# R3-URC18-V1.net
KiCad netlist of a schematic drawn in EAGLE
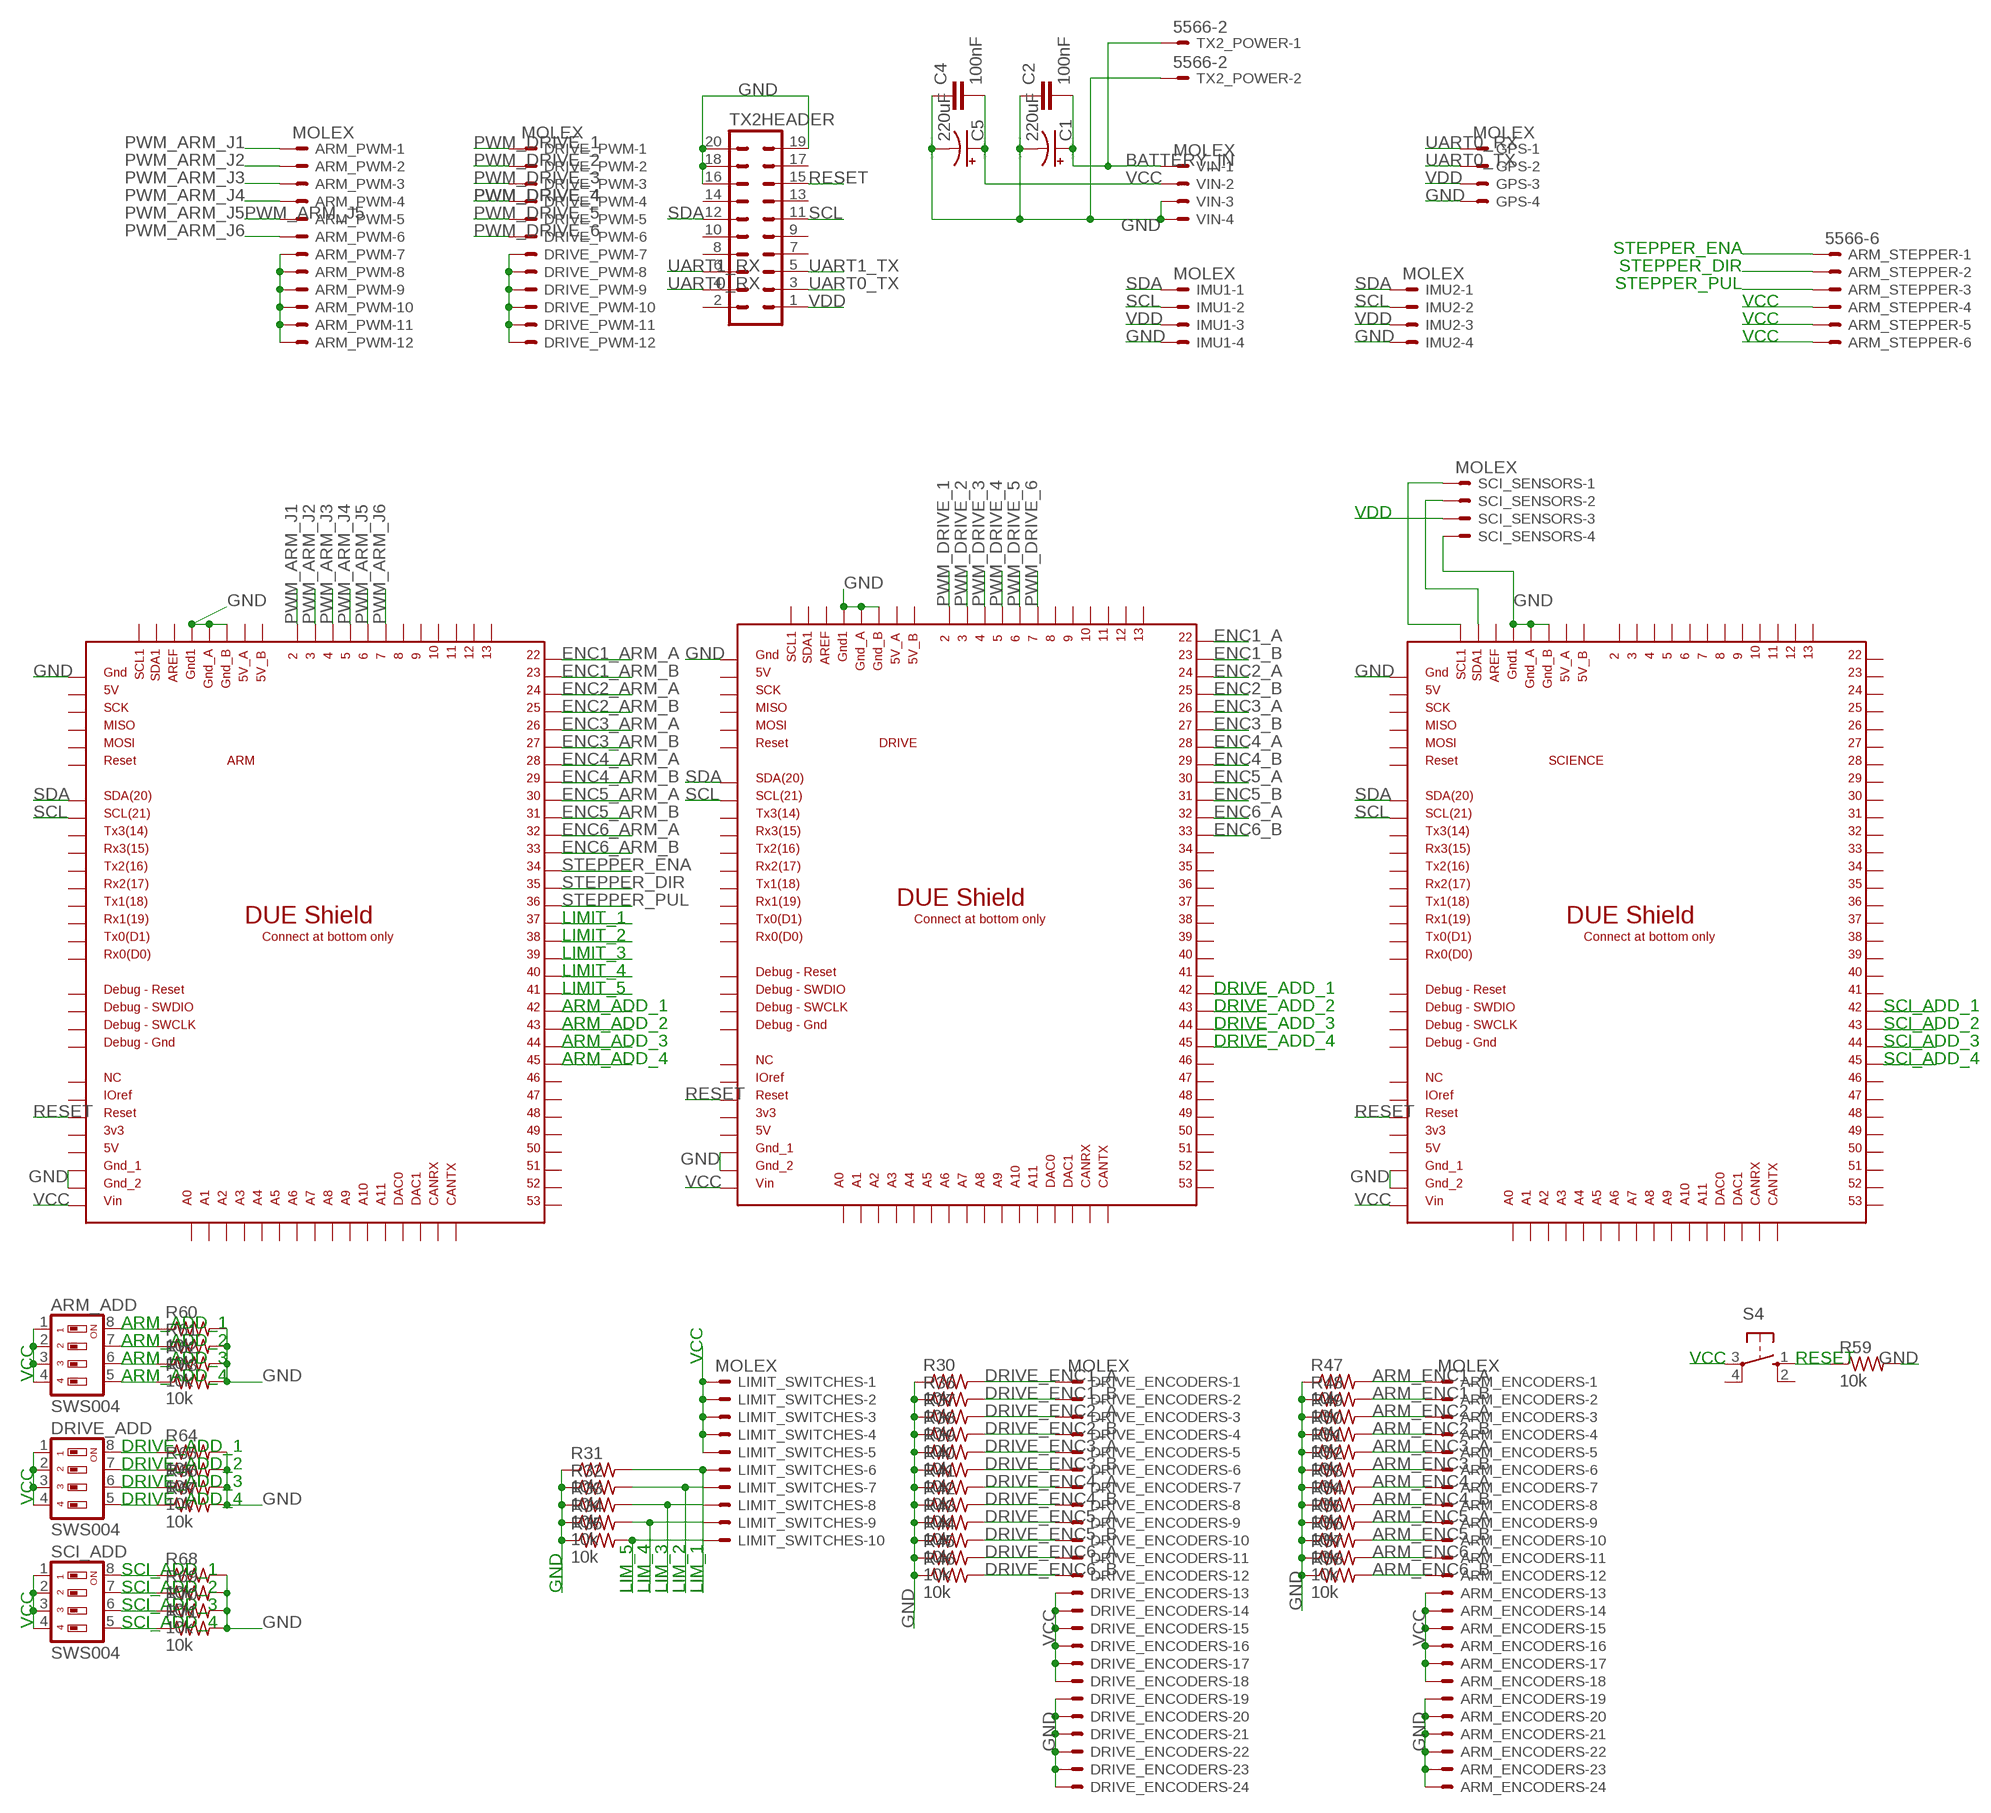
[diagram p0: schematic, sheet 1, part 1 of 2]
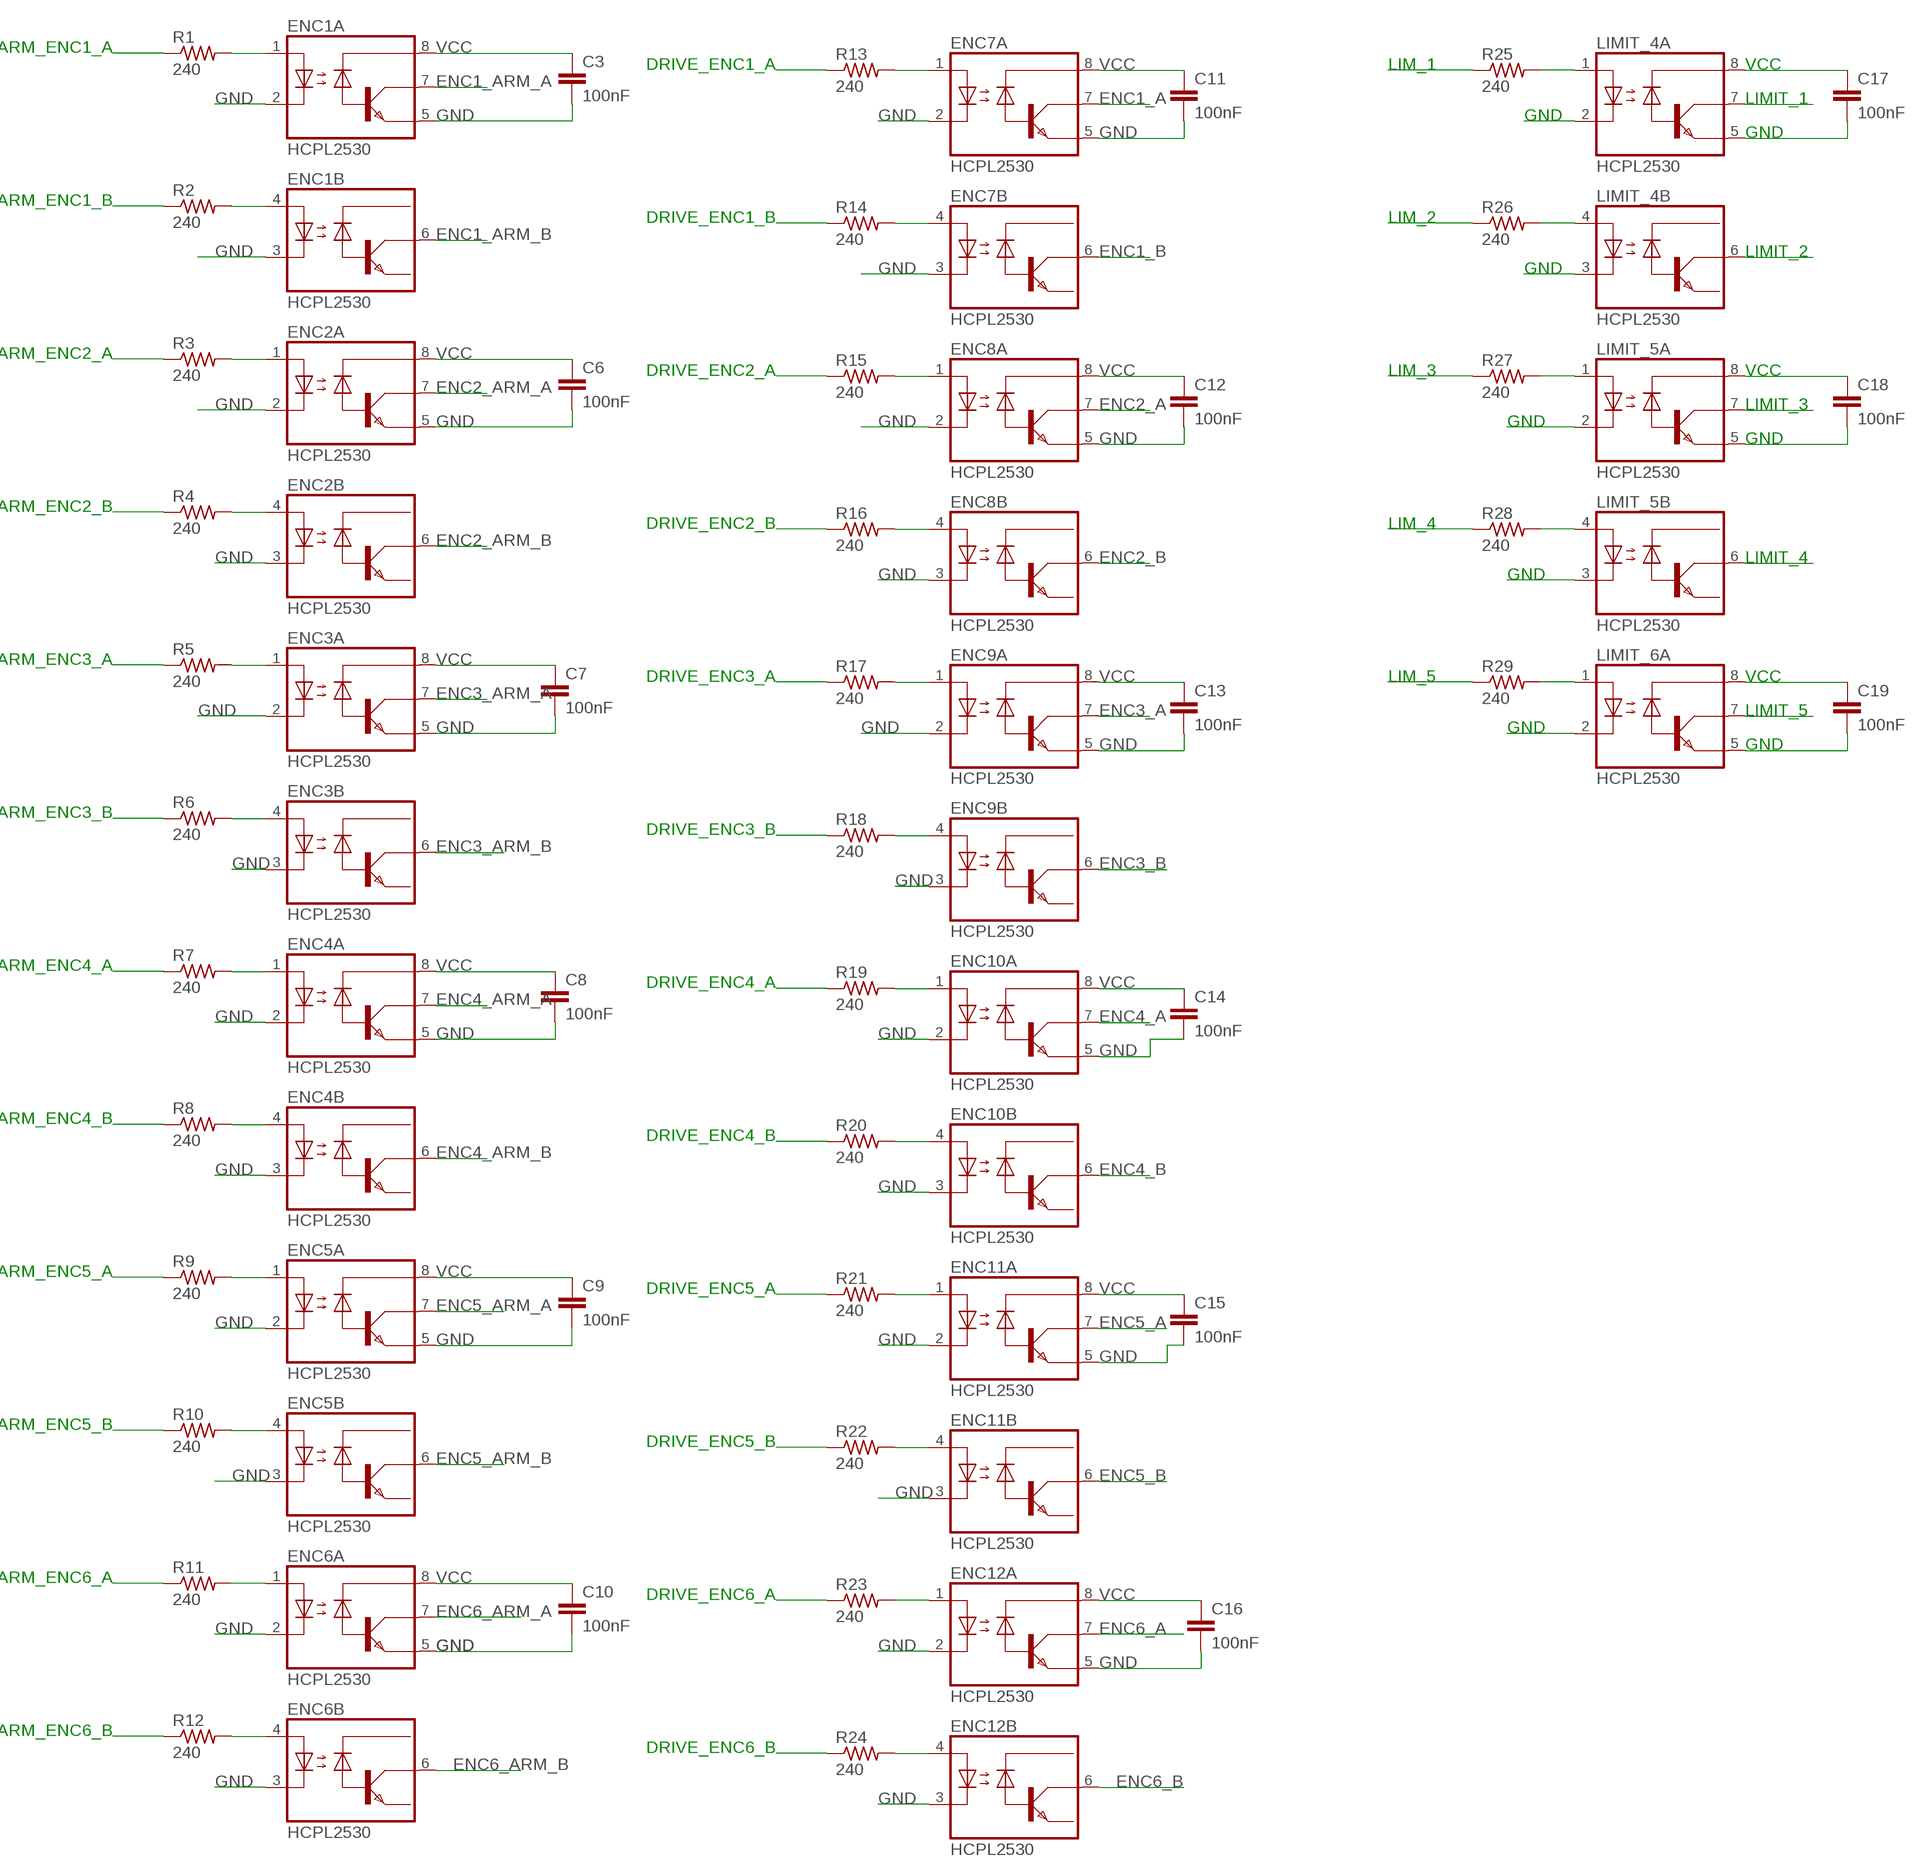
[diagram p1: schematic, sheet 1, part 2 of 2]

(export (version "E")
  (design (tool "Eeschema 10.0.6"))
  (components
    (comp (ref "ARM")
      (value "DUE(BOTTOMONLY)")
      (footprint "eagle-import:DUE(BOTTOMONLY)")
      (libsource (lib "eagle-import") (part "DUE(BOTTOMONLY)"))
    )
    (comp (ref "ARM_ADD")
      (value "SWS004")
      (footprint "eagle-import:SMS-004")
      (libsource (lib "eagle-import") (part "SWS004"))
    )
    (comp (ref "ARM_ENCODERS")
      (value "MOLEX")
      (footprint "eagle-import:5566-24")
      (libsource (lib "eagle-import") (part "5566-24"))
    )
    (comp (ref "ARM_PWM")
      (value "MOLEX")
      (footprint "eagle-import:5566-12")
      (libsource (lib "eagle-import") (part "5566-12"))
    )
    (comp (ref "ARM_STEPPER")
      (value "5566-6")
      (footprint "eagle-import:5566-6")
      (fields (field (name "MF") "MOLEX") (field (name "MPN") "95566-61002"))
      (libsource (lib "eagle-import") (part "5566-6"))
    )
    (comp (ref "C1")
      (value "220uF")
      (footprint "eagle-import:E7,5-18")
      (libsource (lib "eagle-import") (part "CPOL-USE7.5-18"))
    )
    (comp (ref "C2")
      (value "100nF")
      (footprint "eagle-import:C2.5-5")
      (libsource (lib "eagle-import") (part "C2.5/5"))
    )
    (comp (ref "C3")
      (value "100nF")
      (footprint "eagle-import:C2.5-5")
      (libsource (lib "eagle-import") (part "C2.5/5"))
    )
    (comp (ref "C4")
      (value "100nF")
      (footprint "eagle-import:C2.5-5")
      (libsource (lib "eagle-import") (part "C2.5/5"))
    )
    (comp (ref "C5")
      (value "220uF")
      (footprint "eagle-import:E7,5-18")
      (libsource (lib "eagle-import") (part "CPOL-USE7.5-18"))
    )
    (comp (ref "C6")
      (value "100nF")
      (footprint "eagle-import:C2.5-5")
      (libsource (lib "eagle-import") (part "C2.5/5"))
    )
    (comp (ref "C7")
      (value "100nF")
      (footprint "eagle-import:C2.5-5")
      (libsource (lib "eagle-import") (part "C2.5/5"))
    )
    (comp (ref "C8")
      (value "100nF")
      (footprint "eagle-import:C2.5-5")
      (libsource (lib "eagle-import") (part "C2.5/5"))
    )
    (comp (ref "C9")
      (value "100nF")
      (footprint "eagle-import:C2.5-5")
      (libsource (lib "eagle-import") (part "C2.5/5"))
    )
    (comp (ref "C10")
      (value "100nF")
      (footprint "eagle-import:C2.5-5")
      (libsource (lib "eagle-import") (part "C2.5/5"))
    )
    (comp (ref "C11")
      (value "100nF")
      (footprint "eagle-import:C2.5-5")
      (libsource (lib "eagle-import") (part "C2.5/5"))
    )
    (comp (ref "C12")
      (value "100nF")
      (footprint "eagle-import:C2.5-5")
      (libsource (lib "eagle-import") (part "C2.5/5"))
    )
    (comp (ref "C13")
      (value "100nF")
      (footprint "eagle-import:C2.5-5")
      (libsource (lib "eagle-import") (part "C2.5/5"))
    )
    (comp (ref "C14")
      (value "100nF")
      (footprint "eagle-import:C2.5-5")
      (libsource (lib "eagle-import") (part "C2.5/5"))
    )
    (comp (ref "C15")
      (value "100nF")
      (footprint "eagle-import:C2.5-5")
      (libsource (lib "eagle-import") (part "C2.5/5"))
    )
    (comp (ref "C16")
      (value "100nF")
      (footprint "eagle-import:C2.5-5")
      (libsource (lib "eagle-import") (part "C2.5/5"))
    )
    (comp (ref "C17")
      (value "100nF")
      (footprint "eagle-import:C2.5-5")
      (libsource (lib "eagle-import") (part "C2.5/5"))
    )
    (comp (ref "C18")
      (value "100nF")
      (footprint "eagle-import:C2.5-5")
      (libsource (lib "eagle-import") (part "C2.5/5"))
    )
    (comp (ref "C19")
      (value "100nF")
      (footprint "eagle-import:C2.5-5")
      (libsource (lib "eagle-import") (part "C2.5/5"))
    )
    (comp (ref "DRIVE")
      (value "DUE(BOTTOMONLY)")
      (footprint "eagle-import:DUE(BOTTOMONLY)")
      (libsource (lib "eagle-import") (part "DUE(BOTTOMONLY)"))
    )
    (comp (ref "DRIVE_ADD")
      (value "SWS004")
      (footprint "eagle-import:SMS-004")
      (libsource (lib "eagle-import") (part "SWS004"))
    )
    (comp (ref "DRIVE_ENCODERS")
      (value "MOLEX")
      (footprint "eagle-import:5566-24")
      (libsource (lib "eagle-import") (part "5566-24"))
    )
    (comp (ref "DRIVE_PWM")
      (value "MOLEX")
      (footprint "eagle-import:5566-12")
      (libsource (lib "eagle-import") (part "5566-12"))
    )
    (comp (ref "ENC1")
      (value "HCPL2530")
      (footprint "eagle-import:DIL08")
      (fields (field (name "MF") "AGILENT TECHNOLOGIES") (field (name "MPN") "HCPL-2530-000E"))
      (libsource (lib "eagle-import") (part "HCPL2530"))
    )
    (comp (ref "ENC2")
      (value "HCPL2530")
      (footprint "eagle-import:DIL08")
      (fields (field (name "MF") "AGILENT TECHNOLOGIES") (field (name "MPN") "HCPL-2530-000E"))
      (libsource (lib "eagle-import") (part "HCPL2530"))
    )
    (comp (ref "ENC3")
      (value "HCPL2530")
      (footprint "eagle-import:DIL08")
      (fields (field (name "MF") "AGILENT TECHNOLOGIES") (field (name "MPN") "HCPL-2530-000E"))
      (libsource (lib "eagle-import") (part "HCPL2530"))
    )
    (comp (ref "ENC4")
      (value "HCPL2530")
      (footprint "eagle-import:DIL08")
      (fields (field (name "MF") "AGILENT TECHNOLOGIES") (field (name "MPN") "HCPL-2530-000E"))
      (libsource (lib "eagle-import") (part "HCPL2530"))
    )
    (comp (ref "ENC5")
      (value "HCPL2530")
      (footprint "eagle-import:DIL08")
      (fields (field (name "MF") "AGILENT TECHNOLOGIES") (field (name "MPN") "HCPL-2530-000E"))
      (libsource (lib "eagle-import") (part "HCPL2530"))
    )
    (comp (ref "ENC6")
      (value "HCPL2530")
      (footprint "eagle-import:DIL08")
      (fields (field (name "MF") "AGILENT TECHNOLOGIES") (field (name "MPN") "HCPL-2530-000E"))
      (libsource (lib "eagle-import") (part "HCPL2530"))
    )
    (comp (ref "ENC7")
      (value "HCPL2530")
      (footprint "eagle-import:DIL08")
      (fields (field (name "MF") "AGILENT TECHNOLOGIES") (field (name "MPN") "HCPL-2530-000E"))
      (libsource (lib "eagle-import") (part "HCPL2530"))
    )
    (comp (ref "ENC8")
      (value "HCPL2530")
      (footprint "eagle-import:DIL08")
      (fields (field (name "MF") "AGILENT TECHNOLOGIES") (field (name "MPN") "HCPL-2530-000E"))
      (libsource (lib "eagle-import") (part "HCPL2530"))
    )
    (comp (ref "ENC9")
      (value "HCPL2530")
      (footprint "eagle-import:DIL08")
      (fields (field (name "MF") "AGILENT TECHNOLOGIES") (field (name "MPN") "HCPL-2530-000E"))
      (libsource (lib "eagle-import") (part "HCPL2530"))
    )
    (comp (ref "ENC10")
      (value "HCPL2530")
      (footprint "eagle-import:DIL08")
      (fields (field (name "MF") "AGILENT TECHNOLOGIES") (field (name "MPN") "HCPL-2530-000E"))
      (libsource (lib "eagle-import") (part "HCPL2530"))
    )
    (comp (ref "ENC11")
      (value "HCPL2530")
      (footprint "eagle-import:DIL08")
      (fields (field (name "MF") "AGILENT TECHNOLOGIES") (field (name "MPN") "HCPL-2530-000E"))
      (libsource (lib "eagle-import") (part "HCPL2530"))
    )
    (comp (ref "ENC12")
      (value "HCPL2530")
      (footprint "eagle-import:DIL08")
      (fields (field (name "MF") "AGILENT TECHNOLOGIES") (field (name "MPN") "HCPL-2530-000E"))
      (libsource (lib "eagle-import") (part "HCPL2530"))
    )
    (comp (ref "GPS")
      (value "MOLEX")
      (footprint "eagle-import:5566-4")
      (libsource (lib "eagle-import") (part "5566-4"))
    )
    (comp (ref "IMU1")
      (value "MOLEX")
      (footprint "eagle-import:5566-4")
      (libsource (lib "eagle-import") (part "5566-4"))
    )
    (comp (ref "IMU2")
      (value "MOLEX")
      (footprint "eagle-import:5566-4")
      (libsource (lib "eagle-import") (part "5566-4"))
    )
    (comp (ref "LIMIT_4")
      (value "HCPL2530")
      (footprint "eagle-import:DIL08")
      (fields (field (name "MF") "AGILENT TECHNOLOGIES") (field (name "MPN") "HCPL-2530-000E"))
      (libsource (lib "eagle-import") (part "HCPL2530"))
    )
    (comp (ref "LIMIT_5")
      (value "HCPL2530")
      (footprint "eagle-import:DIL08")
      (fields (field (name "MF") "AGILENT TECHNOLOGIES") (field (name "MPN") "HCPL-2530-000E"))
      (libsource (lib "eagle-import") (part "HCPL2530"))
    )
    (comp (ref "LIMIT_6")
      (value "HCPL2530")
      (footprint "eagle-import:DIL08")
      (fields (field (name "MF") "AGILENT TECHNOLOGIES") (field (name "MPN") "HCPL-2530-000E"))
      (libsource (lib "eagle-import") (part "HCPL2530"))
    )
    (comp (ref "LIMIT_SWITCHES")
      (value "MOLEX")
      (footprint "eagle-import:5566-10")
      (libsource (lib "eagle-import") (part "5566-10"))
    )
    (comp (ref "R1")
      (value "240")
      (footprint "eagle-import:0207_10")
      (libsource (lib "eagle-import") (part "R-US_0207/10"))
    )
    (comp (ref "R2")
      (value "240")
      (footprint "eagle-import:0207_10")
      (libsource (lib "eagle-import") (part "R-US_0207/10"))
    )
    (comp (ref "R3")
      (value "240")
      (footprint "eagle-import:0207_10")
      (libsource (lib "eagle-import") (part "R-US_0207/10"))
    )
    (comp (ref "R4")
      (value "240")
      (footprint "eagle-import:0207_10")
      (libsource (lib "eagle-import") (part "R-US_0207/10"))
    )
    (comp (ref "R5")
      (value "240")
      (footprint "eagle-import:0207_10")
      (libsource (lib "eagle-import") (part "R-US_0207/10"))
    )
    (comp (ref "R6")
      (value "240")
      (footprint "eagle-import:0207_10")
      (libsource (lib "eagle-import") (part "R-US_0207/10"))
    )
    (comp (ref "R7")
      (value "240")
      (footprint "eagle-import:0207_10")
      (libsource (lib "eagle-import") (part "R-US_0207/10"))
    )
    (comp (ref "R8")
      (value "240")
      (footprint "eagle-import:0207_10")
      (libsource (lib "eagle-import") (part "R-US_0207/10"))
    )
    (comp (ref "R9")
      (value "240")
      (footprint "eagle-import:0207_10")
      (libsource (lib "eagle-import") (part "R-US_0207/10"))
    )
    (comp (ref "R10")
      (value "240")
      (footprint "eagle-import:0207_10")
      (libsource (lib "eagle-import") (part "R-US_0207/10"))
    )
    (comp (ref "R11")
      (value "240")
      (footprint "eagle-import:0207_10")
      (libsource (lib "eagle-import") (part "R-US_0207/10"))
    )
    (comp (ref "R12")
      (value "240")
      (footprint "eagle-import:0207_10")
      (libsource (lib "eagle-import") (part "R-US_0207/10"))
    )
    (comp (ref "R13")
      (value "240")
      (footprint "eagle-import:0207_10")
      (libsource (lib "eagle-import") (part "R-US_0207/10"))
    )
    (comp (ref "R14")
      (value "240")
      (footprint "eagle-import:0207_10")
      (libsource (lib "eagle-import") (part "R-US_0207/10"))
    )
    (comp (ref "R15")
      (value "240")
      (footprint "eagle-import:0207_10")
      (libsource (lib "eagle-import") (part "R-US_0207/10"))
    )
    (comp (ref "R16")
      (value "240")
      (footprint "eagle-import:0207_10")
      (libsource (lib "eagle-import") (part "R-US_0207/10"))
    )
    (comp (ref "R17")
      (value "240")
      (footprint "eagle-import:0207_10")
      (libsource (lib "eagle-import") (part "R-US_0207/10"))
    )
    (comp (ref "R18")
      (value "240")
      (footprint "eagle-import:0207_10")
      (libsource (lib "eagle-import") (part "R-US_0207/10"))
    )
    (comp (ref "R19")
      (value "240")
      (footprint "eagle-import:0207_10")
      (libsource (lib "eagle-import") (part "R-US_0207/10"))
    )
    (comp (ref "R20")
      (value "240")
      (footprint "eagle-import:0207_10")
      (libsource (lib "eagle-import") (part "R-US_0207/10"))
    )
    (comp (ref "R21")
      (value "240")
      (footprint "eagle-import:0207_10")
      (libsource (lib "eagle-import") (part "R-US_0207/10"))
    )
    (comp (ref "R22")
      (value "240")
      (footprint "eagle-import:0207_10")
      (libsource (lib "eagle-import") (part "R-US_0207/10"))
    )
    (comp (ref "R23")
      (value "240")
      (footprint "eagle-import:0207_10")
      (libsource (lib "eagle-import") (part "R-US_0207/10"))
    )
    (comp (ref "R24")
      (value "240")
      (footprint "eagle-import:0207_10")
      (libsource (lib "eagle-import") (part "R-US_0207/10"))
    )
    (comp (ref "R25")
      (value "240")
      (footprint "eagle-import:0207_10")
      (libsource (lib "eagle-import") (part "R-US_0207/10"))
    )
    (comp (ref "R26")
      (value "240")
      (footprint "eagle-import:0207_10")
      (libsource (lib "eagle-import") (part "R-US_0207/10"))
    )
    (comp (ref "R27")
      (value "240")
      (footprint "eagle-import:0207_10")
      (libsource (lib "eagle-import") (part "R-US_0207/10"))
    )
    (comp (ref "R28")
      (value "240")
      (footprint "eagle-import:0207_10")
      (libsource (lib "eagle-import") (part "R-US_0207/10"))
    )
    (comp (ref "R29")
      (value "240")
      (footprint "eagle-import:0207_10")
      (libsource (lib "eagle-import") (part "R-US_0207/10"))
    )
    (comp (ref "R30")
      (value "10k")
      (footprint "eagle-import:0207_10")
      (libsource (lib "eagle-import") (part "R-US_0207/10"))
    )
    (comp (ref "R31")
      (value "10k")
      (footprint "eagle-import:0207_10")
      (libsource (lib "eagle-import") (part "R-US_0207/10"))
    )
    (comp (ref "R32")
      (value "10k")
      (footprint "eagle-import:0207_10")
      (libsource (lib "eagle-import") (part "R-US_0207/10"))
    )
    (comp (ref "R33")
      (value "10k")
      (footprint "eagle-import:0207_10")
      (libsource (lib "eagle-import") (part "R-US_0207/10"))
    )
    (comp (ref "R34")
      (value "10k")
      (footprint "eagle-import:0207_10")
      (libsource (lib "eagle-import") (part "R-US_0207/10"))
    )
    (comp (ref "R35")
      (value "10k")
      (footprint "eagle-import:0207_10")
      (libsource (lib "eagle-import") (part "R-US_0207/10"))
    )
    (comp (ref "R36")
      (value "10k")
      (footprint "eagle-import:0207_10")
      (libsource (lib "eagle-import") (part "R-US_0207/10"))
    )
    (comp (ref "R37")
      (value "10k")
      (footprint "eagle-import:0207_10")
      (libsource (lib "eagle-import") (part "R-US_0207/10"))
    )
    (comp (ref "R38")
      (value "10k")
      (footprint "eagle-import:0207_10")
      (libsource (lib "eagle-import") (part "R-US_0207/10"))
    )
    (comp (ref "R39")
      (value "10k")
      (footprint "eagle-import:0207_10")
      (libsource (lib "eagle-import") (part "R-US_0207/10"))
    )
    (comp (ref "R40")
      (value "10k")
      (footprint "eagle-import:0207_10")
      (libsource (lib "eagle-import") (part "R-US_0207/10"))
    )
    (comp (ref "R41")
      (value "10k")
      (footprint "eagle-import:0207_10")
      (libsource (lib "eagle-import") (part "R-US_0207/10"))
    )
    (comp (ref "R42")
      (value "10k")
      (footprint "eagle-import:0207_10")
      (libsource (lib "eagle-import") (part "R-US_0207/10"))
    )
    (comp (ref "R43")
      (value "10k")
      (footprint "eagle-import:0207_10")
      (libsource (lib "eagle-import") (part "R-US_0207/10"))
    )
    (comp (ref "R44")
      (value "10k")
      (footprint "eagle-import:0207_10")
      (libsource (lib "eagle-import") (part "R-US_0207/10"))
    )
    (comp (ref "R45")
      (value "10k")
      (footprint "eagle-import:0207_10")
      (libsource (lib "eagle-import") (part "R-US_0207/10"))
    )
    (comp (ref "R46")
      (value "10k")
      (footprint "eagle-import:0207_10")
      (libsource (lib "eagle-import") (part "R-US_0207/10"))
    )
    (comp (ref "R47")
      (value "10k")
      (footprint "eagle-import:0207_10")
      (libsource (lib "eagle-import") (part "R-US_0207/10"))
    )
    (comp (ref "R48")
      (value "10k")
      (footprint "eagle-import:0207_10")
      (libsource (lib "eagle-import") (part "R-US_0207/10"))
    )
    (comp (ref "R49")
      (value "10k")
      (footprint "eagle-import:0207_10")
      (libsource (lib "eagle-import") (part "R-US_0207/10"))
    )
    (comp (ref "R50")
      (value "10k")
      (footprint "eagle-import:0207_10")
      (libsource (lib "eagle-import") (part "R-US_0207/10"))
    )
    (comp (ref "R51")
      (value "10k")
      (footprint "eagle-import:0207_10")
      (libsource (lib "eagle-import") (part "R-US_0207/10"))
    )
    (comp (ref "R52")
      (value "10k")
      (footprint "eagle-import:0207_10")
      (libsource (lib "eagle-import") (part "R-US_0207/10"))
    )
    (comp (ref "R53")
      (value "10k")
      (footprint "eagle-import:0207_10")
      (libsource (lib "eagle-import") (part "R-US_0207/10"))
    )
    (comp (ref "R54")
      (value "10k")
      (footprint "eagle-import:0207_10")
      (libsource (lib "eagle-import") (part "R-US_0207/10"))
    )
    (comp (ref "R55")
      (value "10k")
      (footprint "eagle-import:0207_10")
      (libsource (lib "eagle-import") (part "R-US_0207/10"))
    )
    (comp (ref "R56")
      (value "10k")
      (footprint "eagle-import:0207_10")
      (libsource (lib "eagle-import") (part "R-US_0207/10"))
    )
    (comp (ref "R57")
      (value "10k")
      (footprint "eagle-import:0207_10")
      (libsource (lib "eagle-import") (part "R-US_0207/10"))
    )
    (comp (ref "R58")
      (value "10k")
      (footprint "eagle-import:0207_10")
      (libsource (lib "eagle-import") (part "R-US_0207/10"))
    )
    (comp (ref "R59")
      (value "10k")
      (footprint "eagle-import:0207_10")
      (libsource (lib "eagle-import") (part "R-US_0207/10"))
    )
    (comp (ref "R60")
      (value "10k")
      (footprint "eagle-import:0207_10")
      (libsource (lib "eagle-import") (part "R-US_0207/10"))
    )
    (comp (ref "R61")
      (value "10k")
      (footprint "eagle-import:0207_10")
      (libsource (lib "eagle-import") (part "R-US_0207/10"))
    )
    (comp (ref "R62")
      (value "10k")
      (footprint "eagle-import:0207_10")
      (libsource (lib "eagle-import") (part "R-US_0207/10"))
    )
    (comp (ref "R63")
      (value "10k")
      (footprint "eagle-import:0207_10")
      (libsource (lib "eagle-import") (part "R-US_0207/10"))
    )
    (comp (ref "R64")
      (value "10k")
      (footprint "eagle-import:0207_10")
      (libsource (lib "eagle-import") (part "R-US_0207/10"))
    )
    (comp (ref "R65")
      (value "10k")
      (footprint "eagle-import:0207_10")
      (libsource (lib "eagle-import") (part "R-US_0207/10"))
    )
    (comp (ref "R66")
      (value "10k")
      (footprint "eagle-import:0207_10")
      (libsource (lib "eagle-import") (part "R-US_0207/10"))
    )
    (comp (ref "R67")
      (value "10k")
      (footprint "eagle-import:0207_10")
      (libsource (lib "eagle-import") (part "R-US_0207/10"))
    )
    (comp (ref "R68")
      (value "10k")
      (footprint "eagle-import:0207_10")
      (libsource (lib "eagle-import") (part "R-US_0207/10"))
    )
    (comp (ref "R69")
      (value "10k")
      (footprint "eagle-import:0207_10")
      (libsource (lib "eagle-import") (part "R-US_0207/10"))
    )
    (comp (ref "R70")
      (value "10k")
      (footprint "eagle-import:0207_10")
      (libsource (lib "eagle-import") (part "R-US_0207/10"))
    )
    (comp (ref "R71")
      (value "10k")
      (footprint "eagle-import:0207_10")
      (libsource (lib "eagle-import") (part "R-US_0207/10"))
    )
    (comp (ref "S4")
      (value "10-XX")
      (footprint "eagle-import:B3F-10XX")
      (fields (field (name "MPN") "B3F-1000"))
      (libsource (lib "eagle-import") (part "10-XX"))
    )
    (comp (ref "SCIENCE")
      (value "DUE(BOTTOMONLY)")
      (footprint "eagle-import:DUE(BOTTOMONLY)")
      (libsource (lib "eagle-import") (part "DUE(BOTTOMONLY)"))
    )
    (comp (ref "SCI_ADD")
      (value "SWS004")
      (footprint "eagle-import:SMS-004")
      (libsource (lib "eagle-import") (part "SWS004"))
    )
    (comp (ref "SCI_SENSORS")
      (value "MOLEX")
      (footprint "eagle-import:5566-4")
      (libsource (lib "eagle-import") (part "5566-4"))
    )
    (comp (ref "TX2HEADER")
      (value "MA10-2")
      (footprint "eagle-import:MA10-2")
      (libsource (lib "eagle-import") (part "MA10-2"))
    )
    (comp (ref "TX2_POWER")
      (value "5566-2")
      (footprint "eagle-import:5566-2")
      (fields (field (name "MF") "MOLEX"))
      (libsource (lib "eagle-import") (part "5566-2"))
    )
    (comp (ref "VIN")
      (value "MOLEX")
      (footprint "eagle-import:5566-4")
      (libsource (lib "eagle-import") (part "5566-4"))
    )
  )
  (nets
    (net (code "1") (name "/ARM_ADD_1") (class "Default")
      (node (ref "ARM") (pin "42") (pinfunction "42_42") (pintype "bidirectional"))
      (node (ref "ARM_ADD") (pin "8") (pinfunction "8_8") (pintype "passive"))
      (node (ref "R60") (pin "1") (pinfunction "1_1") (pintype "passive"))
    )
    (net (code "2") (name "/ARM_ADD_2") (class "Default")
      (node (ref "ARM") (pin "43") (pinfunction "43_43") (pintype "bidirectional"))
      (node (ref "ARM_ADD") (pin "7") (pinfunction "7_7") (pintype "passive"))
      (node (ref "R61") (pin "1") (pinfunction "1_1") (pintype "passive"))
    )
    (net (code "3") (name "/ARM_ADD_3") (class "Default")
      (node (ref "ARM") (pin "44") (pinfunction "44_44") (pintype "bidirectional"))
      (node (ref "ARM_ADD") (pin "6") (pinfunction "6_6") (pintype "passive"))
      (node (ref "R62") (pin "1") (pinfunction "1_1") (pintype "passive"))
    )
    (net (code "4") (name "/ARM_ADD_4") (class "Default")
      (node (ref "ARM") (pin "45") (pinfunction "45_45") (pintype "bidirectional"))
      (node (ref "ARM_ADD") (pin "5") (pinfunction "5_5") (pintype "passive"))
      (node (ref "R63") (pin "1") (pinfunction "1_1") (pintype "passive"))
    )
    (net (code "5") (name "/ARM_ENC1_A") (class "Default")
      (node (ref "ARM_ENCODERS") (pin "1") (pinfunction "S_1") (pintype "passive"))
      (node (ref "R1") (pin "1") (pinfunction "1_1") (pintype "passive"))
      (node (ref "R47") (pin "2") (pinfunction "2_2") (pintype "passive"))
    )
    (net (code "6") (name "/ARM_ENC1_B") (class "Default")
      (node (ref "ARM_ENCODERS") (pin "2") (pinfunction "S_2") (pintype "passive"))
      (node (ref "R2") (pin "1") (pinfunction "1_1") (pintype "passive"))
      (node (ref "R48") (pin "2") (pinfunction "2_2") (pintype "passive"))
    )
    (net (code "7") (name "/ARM_ENC2_A") (class "Default")
      (node (ref "ARM_ENCODERS") (pin "3") (pinfunction "S_3") (pintype "passive"))
      (node (ref "R3") (pin "1") (pinfunction "1_1") (pintype "passive"))
      (node (ref "R49") (pin "2") (pinfunction "2_2") (pintype "passive"))
    )
    (net (code "8") (name "/ARM_ENC2_B") (class "Default")
      (node (ref "ARM_ENCODERS") (pin "4") (pinfunction "S_4") (pintype "passive"))
      (node (ref "R4") (pin "1") (pinfunction "1_1") (pintype "passive"))
      (node (ref "R50") (pin "2") (pinfunction "2_2") (pintype "passive"))
    )
    (net (code "9") (name "/ARM_ENC3_A") (class "Default")
      (node (ref "ARM_ENCODERS") (pin "5") (pinfunction "S_5") (pintype "passive"))
      (node (ref "R5") (pin "1") (pinfunction "1_1") (pintype "passive"))
      (node (ref "R51") (pin "2") (pinfunction "2_2") (pintype "passive"))
    )
    (net (code "10") (name "/ARM_ENC3_B") (class "Default")
      (node (ref "ARM_ENCODERS") (pin "6") (pinfunction "S_6") (pintype "passive"))
      (node (ref "R52") (pin "2") (pinfunction "2_2") (pintype "passive"))
      (node (ref "R6") (pin "1") (pinfunction "1_1") (pintype "passive"))
    )
    (net (code "11") (name "/ARM_ENC4_A") (class "Default")
      (node (ref "ARM_ENCODERS") (pin "7") (pinfunction "S_7") (pintype "passive"))
      (node (ref "R53") (pin "2") (pinfunction "2_2") (pintype "passive"))
      (node (ref "R7") (pin "1") (pinfunction "1_1") (pintype "passive"))
    )
    (net (code "12") (name "/ARM_ENC4_B") (class "Default")
      (node (ref "ARM_ENCODERS") (pin "8") (pinfunction "S_8") (pintype "passive"))
      (node (ref "R54") (pin "2") (pinfunction "2_2") (pintype "passive"))
      (node (ref "R8") (pin "1") (pinfunction "1_1") (pintype "passive"))
    )
    (net (code "13") (name "/ARM_ENC5_A") (class "Default")
      (node (ref "ARM_ENCODERS") (pin "9") (pinfunction "S_9") (pintype "passive"))
      (node (ref "R55") (pin "2") (pinfunction "2_2") (pintype "passive"))
      (node (ref "R9") (pin "1") (pinfunction "1_1") (pintype "passive"))
    )
    (net (code "14") (name "/ARM_ENC5_B") (class "Default")
      (node (ref "ARM_ENCODERS") (pin "10") (pinfunction "S_10") (pintype "passive"))
      (node (ref "R10") (pin "1") (pinfunction "1_1") (pintype "passive"))
      (node (ref "R56") (pin "2") (pinfunction "2_2") (pintype "passive"))
    )
    (net (code "15") (name "/ARM_ENC6_A") (class "Default")
      (node (ref "ARM_ENCODERS") (pin "11") (pinfunction "S_11") (pintype "passive"))
      (node (ref "R11") (pin "1") (pinfunction "1_1") (pintype "passive"))
      (node (ref "R57") (pin "2") (pinfunction "2_2") (pintype "passive"))
    )
    (net (code "16") (name "/ARM_ENC6_B") (class "Default")
      (node (ref "ARM_ENCODERS") (pin "12") (pinfunction "S_12") (pintype "passive"))
      (node (ref "R12") (pin "1") (pinfunction "1_1") (pintype "passive"))
      (node (ref "R58") (pin "2") (pinfunction "2_2") (pintype "passive"))
    )
    (net (code "17") (name "/BATTERY_IN") (class "Default")
      (node (ref "C1") (pin "+") (pinfunction "+_+") (pintype "passive"))
      (node (ref "C2") (pin "2") (pinfunction "2_2") (pintype "passive"))
      (node (ref "TX2_POWER") (pin "1") (pinfunction "S_1") (pintype "passive"))
      (node (ref "VIN") (pin "1") (pinfunction "S_1") (pintype "passive"))
    )
    (net (code "18") (name "/DRIVE_ADD_1") (class "Default")
      (node (ref "DRIVE") (pin "42") (pinfunction "42_42") (pintype "bidirectional"))
      (node (ref "DRIVE_ADD") (pin "8") (pinfunction "8_8") (pintype "passive"))
      (node (ref "R64") (pin "1") (pinfunction "1_1") (pintype "passive"))
    )
    (net (code "19") (name "/DRIVE_ADD_2") (class "Default")
      (node (ref "DRIVE") (pin "43") (pinfunction "43_43") (pintype "bidirectional"))
      (node (ref "DRIVE_ADD") (pin "7") (pinfunction "7_7") (pintype "passive"))
      (node (ref "R65") (pin "1") (pinfunction "1_1") (pintype "passive"))
    )
    (net (code "20") (name "/DRIVE_ADD_3") (class "Default")
      (node (ref "DRIVE") (pin "44") (pinfunction "44_44") (pintype "bidirectional"))
      (node (ref "DRIVE_ADD") (pin "6") (pinfunction "6_6") (pintype "passive"))
      (node (ref "R66") (pin "1") (pinfunction "1_1") (pintype "passive"))
    )
    (net (code "21") (name "/DRIVE_ADD_4") (class "Default")
      (node (ref "DRIVE") (pin "45") (pinfunction "45_45") (pintype "bidirectional"))
      (node (ref "DRIVE_ADD") (pin "5") (pinfunction "5_5") (pintype "passive"))
      (node (ref "R67") (pin "1") (pinfunction "1_1") (pintype "passive"))
    )
    (net (code "22") (name "/DRIVE_ENC1_A") (class "Default")
      (node (ref "DRIVE_ENCODERS") (pin "1") (pinfunction "S_1") (pintype "passive"))
      (node (ref "R13") (pin "1") (pinfunction "1_1") (pintype "passive"))
      (node (ref "R30") (pin "2") (pinfunction "2_2") (pintype "passive"))
    )
    (net (code "23") (name "/DRIVE_ENC1_B") (class "Default")
      (node (ref "DRIVE_ENCODERS") (pin "2") (pinfunction "S_2") (pintype "passive"))
      (node (ref "R14") (pin "1") (pinfunction "1_1") (pintype "passive"))
      (node (ref "R36") (pin "2") (pinfunction "2_2") (pintype "passive"))
    )
    (net (code "24") (name "/DRIVE_ENC2_A") (class "Default")
      (node (ref "DRIVE_ENCODERS") (pin "3") (pinfunction "S_3") (pintype "passive"))
      (node (ref "R15") (pin "1") (pinfunction "1_1") (pintype "passive"))
      (node (ref "R37") (pin "2") (pinfunction "2_2") (pintype "passive"))
    )
    (net (code "25") (name "/DRIVE_ENC2_B") (class "Default")
      (node (ref "DRIVE_ENCODERS") (pin "4") (pinfunction "S_4") (pintype "passive"))
      (node (ref "R16") (pin "1") (pinfunction "1_1") (pintype "passive"))
      (node (ref "R38") (pin "2") (pinfunction "2_2") (pintype "passive"))
    )
    (net (code "26") (name "/DRIVE_ENC3_A") (class "Default")
      (node (ref "DRIVE_ENCODERS") (pin "5") (pinfunction "S_5") (pintype "passive"))
      (node (ref "R17") (pin "1") (pinfunction "1_1") (pintype "passive"))
      (node (ref "R39") (pin "2") (pinfunction "2_2") (pintype "passive"))
    )
    (net (code "27") (name "/DRIVE_ENC3_B") (class "Default")
      (node (ref "DRIVE_ENCODERS") (pin "6") (pinfunction "S_6") (pintype "passive"))
      (node (ref "R18") (pin "1") (pinfunction "1_1") (pintype "passive"))
      (node (ref "R40") (pin "2") (pinfunction "2_2") (pintype "passive"))
    )
    (net (code "28") (name "/DRIVE_ENC4_A") (class "Default")
      (node (ref "DRIVE_ENCODERS") (pin "7") (pinfunction "S_7") (pintype "passive"))
      (node (ref "R19") (pin "1") (pinfunction "1_1") (pintype "passive"))
      (node (ref "R41") (pin "2") (pinfunction "2_2") (pintype "passive"))
    )
    (net (code "29") (name "/DRIVE_ENC4_B") (class "Default")
      (node (ref "DRIVE_ENCODERS") (pin "8") (pinfunction "S_8") (pintype "passive"))
      (node (ref "R20") (pin "1") (pinfunction "1_1") (pintype "passive"))
      (node (ref "R42") (pin "2") (pinfunction "2_2") (pintype "passive"))
    )
    (net (code "30") (name "/DRIVE_ENC5_A") (class "Default")
      (node (ref "DRIVE_ENCODERS") (pin "9") (pinfunction "S_9") (pintype "passive"))
      (node (ref "R21") (pin "1") (pinfunction "1_1") (pintype "passive"))
      (node (ref "R43") (pin "2") (pinfunction "2_2") (pintype "passive"))
    )
    (net (code "31") (name "/DRIVE_ENC5_B") (class "Default")
      (node (ref "DRIVE_ENCODERS") (pin "10") (pinfunction "S_10") (pintype "passive"))
      (node (ref "R22") (pin "1") (pinfunction "1_1") (pintype "passive"))
      (node (ref "R44") (pin "2") (pinfunction "2_2") (pintype "passive"))
    )
    (net (code "32") (name "/DRIVE_ENC6_A") (class "Default")
      (node (ref "DRIVE_ENCODERS") (pin "11") (pinfunction "S_11") (pintype "passive"))
      (node (ref "R23") (pin "1") (pinfunction "1_1") (pintype "passive"))
      (node (ref "R45") (pin "2") (pinfunction "2_2") (pintype "passive"))
    )
    (net (code "33") (name "/DRIVE_ENC6_B") (class "Default")
      (node (ref "DRIVE_ENCODERS") (pin "12") (pinfunction "S_12") (pintype "passive"))
      (node (ref "R24") (pin "1") (pinfunction "1_1") (pintype "passive"))
      (node (ref "R46") (pin "2") (pinfunction "2_2") (pintype "passive"))
    )
    (net (code "34") (name "/ENC1_A") (class "Default")
      (node (ref "DRIVE") (pin "22") (pinfunction "22_22") (pintype "bidirectional"))
      (node (ref "ENC7") (pin "7") (pinfunction "VO1_7") (pintype "passive"))
    )
    (net (code "35") (name "/ENC1_ARM_A") (class "Default")
      (node (ref "ARM") (pin "22") (pinfunction "22_22") (pintype "bidirectional"))
      (node (ref "ENC1") (pin "7") (pinfunction "VO1_7") (pintype "passive"))
    )
    (net (code "36") (name "/ENC1_ARM_B") (class "Default")
      (node (ref "ARM") (pin "23") (pinfunction "23_23") (pintype "bidirectional"))
      (node (ref "ENC1") (pin "6") (pinfunction "VO2_6") (pintype "passive"))
    )
    (net (code "37") (name "/ENC1_B") (class "Default")
      (node (ref "DRIVE") (pin "23") (pinfunction "23_23") (pintype "bidirectional"))
      (node (ref "ENC7") (pin "6") (pinfunction "VO2_6") (pintype "passive"))
    )
    (net (code "38") (name "/ENC2_A") (class "Default")
      (node (ref "DRIVE") (pin "24") (pinfunction "24_24") (pintype "bidirectional"))
      (node (ref "ENC8") (pin "7") (pinfunction "VO1_7") (pintype "passive"))
    )
    (net (code "39") (name "/ENC2_ARM_A") (class "Default")
      (node (ref "ARM") (pin "24") (pinfunction "24_24") (pintype "bidirectional"))
      (node (ref "ENC2") (pin "7") (pinfunction "VO1_7") (pintype "passive"))
    )
    (net (code "40") (name "/ENC2_ARM_B") (class "Default")
      (node (ref "ARM") (pin "25") (pinfunction "25_25") (pintype "bidirectional"))
      (node (ref "ENC2") (pin "6") (pinfunction "VO2_6") (pintype "passive"))
    )
    (net (code "41") (name "/ENC2_B") (class "Default")
      (node (ref "DRIVE") (pin "25") (pinfunction "25_25") (pintype "bidirectional"))
      (node (ref "ENC8") (pin "6") (pinfunction "VO2_6") (pintype "passive"))
    )
    (net (code "42") (name "/ENC3_A") (class "Default")
      (node (ref "DRIVE") (pin "26") (pinfunction "26_26") (pintype "bidirectional"))
      (node (ref "ENC9") (pin "7") (pinfunction "VO1_7") (pintype "passive"))
    )
    (net (code "43") (name "/ENC3_ARM_A") (class "Default")
      (node (ref "ARM") (pin "26") (pinfunction "26_26") (pintype "bidirectional"))
      (node (ref "ENC3") (pin "7") (pinfunction "VO1_7") (pintype "passive"))
    )
    (net (code "44") (name "/ENC3_ARM_B") (class "Default")
      (node (ref "ARM") (pin "27") (pinfunction "27_27") (pintype "bidirectional"))
      (node (ref "ENC3") (pin "6") (pinfunction "VO2_6") (pintype "passive"))
    )
    (net (code "45") (name "/ENC3_B") (class "Default")
      (node (ref "DRIVE") (pin "27") (pinfunction "27_27") (pintype "bidirectional"))
      (node (ref "ENC9") (pin "6") (pinfunction "VO2_6") (pintype "passive"))
    )
    (net (code "46") (name "/ENC4_A") (class "Default")
      (node (ref "DRIVE") (pin "28") (pinfunction "28_28") (pintype "bidirectional"))
      (node (ref "ENC10") (pin "7") (pinfunction "VO1_7") (pintype "passive"))
    )
    (net (code "47") (name "/ENC4_ARM_A") (class "Default")
      (node (ref "ARM") (pin "28") (pinfunction "28_28") (pintype "bidirectional"))
      (node (ref "ENC4") (pin "7") (pinfunction "VO1_7") (pintype "passive"))
    )
    (net (code "48") (name "/ENC4_ARM_B") (class "Default")
      (node (ref "ARM") (pin "29") (pinfunction "29_29") (pintype "bidirectional"))
      (node (ref "ENC4") (pin "6") (pinfunction "VO2_6") (pintype "passive"))
    )
    (net (code "49") (name "/ENC4_B") (class "Default")
      (node (ref "DRIVE") (pin "29") (pinfunction "29_29") (pintype "bidirectional"))
      (node (ref "ENC10") (pin "6") (pinfunction "VO2_6") (pintype "passive"))
    )
    (net (code "50") (name "/ENC5_A") (class "Default")
      (node (ref "DRIVE") (pin "30") (pinfunction "30_30") (pintype "bidirectional"))
      (node (ref "ENC11") (pin "7") (pinfunction "VO1_7") (pintype "passive"))
    )
    (net (code "51") (name "/ENC5_ARM_A") (class "Default")
      (node (ref "ARM") (pin "30") (pinfunction "30_30") (pintype "bidirectional"))
      (node (ref "ENC5") (pin "7") (pinfunction "VO1_7") (pintype "passive"))
    )
    (net (code "52") (name "/ENC5_ARM_B") (class "Default")
      (node (ref "ARM") (pin "31") (pinfunction "31_31") (pintype "bidirectional"))
      (node (ref "ENC5") (pin "6") (pinfunction "VO2_6") (pintype "passive"))
    )
    (net (code "53") (name "/ENC5_B") (class "Default")
      (node (ref "DRIVE") (pin "31") (pinfunction "31_31") (pintype "bidirectional"))
      (node (ref "ENC11") (pin "6") (pinfunction "VO2_6") (pintype "passive"))
    )
    (net (code "54") (name "/ENC6_A") (class "Default")
      (node (ref "DRIVE") (pin "32") (pinfunction "32_32") (pintype "bidirectional"))
      (node (ref "ENC12") (pin "7") (pinfunction "VO1_7") (pintype "passive"))
    )
    (net (code "55") (name "/ENC6_ARM_A") (class "Default")
      (node (ref "ARM") (pin "32") (pinfunction "32_32") (pintype "bidirectional"))
      (node (ref "ENC6") (pin "7") (pinfunction "VO1_7") (pintype "passive"))
    )
    (net (code "56") (name "/ENC6_ARM_B") (class "Default")
      (node (ref "ARM") (pin "33") (pinfunction "33_33") (pintype "bidirectional"))
      (node (ref "ENC6") (pin "6") (pinfunction "VO2_6") (pintype "passive"))
    )
    (net (code "57") (name "/ENC6_B") (class "Default")
      (node (ref "DRIVE") (pin "33") (pinfunction "33_33") (pintype "bidirectional"))
      (node (ref "ENC12") (pin "6") (pinfunction "VO2_6") (pintype "passive"))
    )
    (net (code "58") (name "/GND") (class "Default")
      (node (ref "ARM") (pin "5V_ICSP") (pinfunction "5V_ICSP_5V_ICSP") (pintype "bidirectional"))
      (node (ref "ARM") (pin "GND1") (pinfunction "GND1_GND1") (pintype "bidirectional"))
      (node (ref "ARM") (pin "GND_1") (pinfunction "GND_1_GND_1") (pintype "bidirectional"))
      (node (ref "ARM") (pin "GND_2") (pinfunction "GND_2_GND_2") (pintype "bidirectional"))
      (node (ref "ARM") (pin "GND_A") (pinfunction "GND_A_GND_A") (pintype "bidirectional"))
      (node (ref "ARM") (pin "GND_B") (pinfunction "GND_B_GND_B") (pintype "bidirectional"))
      (node (ref "ARM_ENCODERS") (pin "19") (pinfunction "S_19") (pintype "passive"))
      (node (ref "ARM_ENCODERS") (pin "20") (pinfunction "S_20") (pintype "passive"))
      (node (ref "ARM_ENCODERS") (pin "21") (pinfunction "S_21") (pintype "passive"))
      (node (ref "ARM_ENCODERS") (pin "22") (pinfunction "S_22") (pintype "passive"))
      (node (ref "ARM_ENCODERS") (pin "23") (pinfunction "S_23") (pintype "passive"))
      (node (ref "ARM_ENCODERS") (pin "24") (pinfunction "S_24") (pintype "passive"))
      (node (ref "C1") (pin "-") (pinfunction "-_-") (pintype "passive"))
      (node (ref "C10") (pin "2") (pinfunction "2_2") (pintype "passive"))
      (node (ref "C11") (pin "2") (pinfunction "2_2") (pintype "passive"))
      (node (ref "C12") (pin "2") (pinfunction "2_2") (pintype "passive"))
      (node (ref "C13") (pin "2") (pinfunction "2_2") (pintype "passive"))
      (node (ref "C14") (pin "2") (pinfunction "2_2") (pintype "passive"))
      (node (ref "C15") (pin "2") (pinfunction "2_2") (pintype "passive"))
      (node (ref "C16") (pin "2") (pinfunction "2_2") (pintype "passive"))
      (node (ref "C17") (pin "2") (pinfunction "2_2") (pintype "passive"))
      (node (ref "C18") (pin "2") (pinfunction "2_2") (pintype "passive"))
      (node (ref "C19") (pin "2") (pinfunction "2_2") (pintype "passive"))
      (node (ref "C2") (pin "1") (pinfunction "1_1") (pintype "passive"))
      (node (ref "C3") (pin "2") (pinfunction "2_2") (pintype "passive"))
      (node (ref "C4") (pin "1") (pinfunction "1_1") (pintype "passive"))
      (node (ref "C5") (pin "-") (pinfunction "-_-") (pintype "passive"))
      (node (ref "C6") (pin "2") (pinfunction "2_2") (pintype "passive"))
      (node (ref "C7") (pin "2") (pinfunction "2_2") (pintype "passive"))
      (node (ref "C8") (pin "2") (pinfunction "2_2") (pintype "passive"))
      (node (ref "C9") (pin "2") (pinfunction "2_2") (pintype "passive"))
      (node (ref "DRIVE") (pin "5V_ICSP") (pinfunction "5V_ICSP_5V_ICSP") (pintype "bidirectional"))
      (node (ref "DRIVE") (pin "GND1") (pinfunction "GND1_GND1") (pintype "bidirectional"))
      (node (ref "DRIVE") (pin "GND_1") (pinfunction "GND_1_GND_1") (pintype "bidirectional"))
      (node (ref "DRIVE") (pin "GND_2") (pinfunction "GND_2_GND_2") (pintype "bidirectional"))
      (node (ref "DRIVE") (pin "GND_A") (pinfunction "GND_A_GND_A") (pintype "bidirectional"))
      (node (ref "DRIVE") (pin "GND_B") (pinfunction "GND_B_GND_B") (pintype "bidirectional"))
      (node (ref "DRIVE_ENCODERS") (pin "19") (pinfunction "S_19") (pintype "passive"))
      (node (ref "DRIVE_ENCODERS") (pin "20") (pinfunction "S_20") (pintype "passive"))
      (node (ref "DRIVE_ENCODERS") (pin "21") (pinfunction "S_21") (pintype "passive"))
      (node (ref "DRIVE_ENCODERS") (pin "22") (pinfunction "S_22") (pintype "passive"))
      (node (ref "DRIVE_ENCODERS") (pin "23") (pinfunction "S_23") (pintype "passive"))
      (node (ref "DRIVE_ENCODERS") (pin "24") (pinfunction "S_24") (pintype "passive"))
      (node (ref "ENC1") (pin "2") (pinfunction "C1_2") (pintype "passive"))
      (node (ref "ENC1") (pin "3") (pinfunction "C2_3") (pintype "passive"))
      (node (ref "ENC1") (pin "5") (pinfunction "GND_5") (pintype "passive"))
      (node (ref "ENC10") (pin "2") (pinfunction "C1_2") (pintype "passive"))
      (node (ref "ENC10") (pin "3") (pinfunction "C2_3") (pintype "passive"))
      (node (ref "ENC10") (pin "5") (pinfunction "GND_5") (pintype "passive"))
      (node (ref "ENC11") (pin "2") (pinfunction "C1_2") (pintype "passive"))
      (node (ref "ENC11") (pin "3") (pinfunction "C2_3") (pintype "passive"))
      (node (ref "ENC11") (pin "5") (pinfunction "GND_5") (pintype "passive"))
      (node (ref "ENC12") (pin "2") (pinfunction "C1_2") (pintype "passive"))
      (node (ref "ENC12") (pin "3") (pinfunction "C2_3") (pintype "passive"))
      (node (ref "ENC12") (pin "5") (pinfunction "GND_5") (pintype "passive"))
      (node (ref "ENC2") (pin "2") (pinfunction "C1_2") (pintype "passive"))
      (node (ref "ENC2") (pin "3") (pinfunction "C2_3") (pintype "passive"))
      (node (ref "ENC2") (pin "5") (pinfunction "GND_5") (pintype "passive"))
      (node (ref "ENC3") (pin "2") (pinfunction "C1_2") (pintype "passive"))
      (node (ref "ENC3") (pin "3") (pinfunction "C2_3") (pintype "passive"))
      (node (ref "ENC3") (pin "5") (pinfunction "GND_5") (pintype "passive"))
      (node (ref "ENC4") (pin "2") (pinfunction "C1_2") (pintype "passive"))
      (node (ref "ENC4") (pin "3") (pinfunction "C2_3") (pintype "passive"))
      (node (ref "ENC4") (pin "5") (pinfunction "GND_5") (pintype "passive"))
      (node (ref "ENC5") (pin "2") (pinfunction "C1_2") (pintype "passive"))
      (node (ref "ENC5") (pin "3") (pinfunction "C2_3") (pintype "passive"))
      (node (ref "ENC5") (pin "5") (pinfunction "GND_5") (pintype "passive"))
      (node (ref "ENC6") (pin "2") (pinfunction "C1_2") (pintype "passive"))
      (node (ref "ENC6") (pin "3") (pinfunction "C2_3") (pintype "passive"))
      (node (ref "ENC6") (pin "5") (pinfunction "GND_5") (pintype "passive"))
      (node (ref "ENC7") (pin "2") (pinfunction "C1_2") (pintype "passive"))
      (node (ref "ENC7") (pin "3") (pinfunction "C2_3") (pintype "passive"))
      (node (ref "ENC7") (pin "5") (pinfunction "GND_5") (pintype "passive"))
      (node (ref "ENC8") (pin "2") (pinfunction "C1_2") (pintype "passive"))
      (node (ref "ENC8") (pin "3") (pinfunction "C2_3") (pintype "passive"))
      (node (ref "ENC8") (pin "5") (pinfunction "GND_5") (pintype "passive"))
      (node (ref "ENC9") (pin "2") (pinfunction "C1_2") (pintype "passive"))
      (node (ref "ENC9") (pin "3") (pinfunction "C2_3") (pintype "passive"))
      (node (ref "ENC9") (pin "5") (pinfunction "GND_5") (pintype "passive"))
      (node (ref "GPS") (pin "4") (pinfunction "S_4") (pintype "passive"))
      (node (ref "IMU1") (pin "4") (pinfunction "S_4") (pintype "passive"))
      (node (ref "IMU2") (pin "4") (pinfunction "S_4") (pintype "passive"))
      (node (ref "LIMIT_4") (pin "2") (pinfunction "C1_2") (pintype "passive"))
      (node (ref "LIMIT_4") (pin "3") (pinfunction "C2_3") (pintype "passive"))
      (node (ref "LIMIT_4") (pin "5") (pinfunction "GND_5") (pintype "passive"))
      (node (ref "LIMIT_5") (pin "2") (pinfunction "C1_2") (pintype "passive"))
      (node (ref "LIMIT_5") (pin "3") (pinfunction "C2_3") (pintype "passive"))
      (node (ref "LIMIT_5") (pin "5") (pinfunction "GND_5") (pintype "passive"))
      (node (ref "LIMIT_6") (pin "2") (pinfunction "C1_2") (pintype "passive"))
      (node (ref "LIMIT_6") (pin "5") (pinfunction "GND_5") (pintype "passive"))
      (node (ref "R30") (pin "1") (pinfunction "1_1") (pintype "passive"))
      (node (ref "R31") (pin "1") (pinfunction "1_1") (pintype "passive"))
      (node (ref "R32") (pin "1") (pinfunction "1_1") (pintype "passive"))
      (node (ref "R33") (pin "1") (pinfunction "1_1") (pintype "passive"))
      (node (ref "R34") (pin "1") (pinfunction "1_1") (pintype "passive"))
      (node (ref "R35") (pin "1") (pinfunction "1_1") (pintype "passive"))
      (node (ref "R36") (pin "1") (pinfunction "1_1") (pintype "passive"))
      (node (ref "R37") (pin "1") (pinfunction "1_1") (pintype "passive"))
      (node (ref "R38") (pin "1") (pinfunction "1_1") (pintype "passive"))
      (node (ref "R39") (pin "1") (pinfunction "1_1") (pintype "passive"))
      (node (ref "R40") (pin "1") (pinfunction "1_1") (pintype "passive"))
      (node (ref "R41") (pin "1") (pinfunction "1_1") (pintype "passive"))
      (node (ref "R42") (pin "1") (pinfunction "1_1") (pintype "passive"))
      (node (ref "R43") (pin "1") (pinfunction "1_1") (pintype "passive"))
      (node (ref "R44") (pin "1") (pinfunction "1_1") (pintype "passive"))
      (node (ref "R45") (pin "1") (pinfunction "1_1") (pintype "passive"))
      (node (ref "R46") (pin "1") (pinfunction "1_1") (pintype "passive"))
      (node (ref "R47") (pin "1") (pinfunction "1_1") (pintype "passive"))
      (node (ref "R48") (pin "1") (pinfunction "1_1") (pintype "passive"))
      (node (ref "R49") (pin "1") (pinfunction "1_1") (pintype "passive"))
      (node (ref "R50") (pin "1") (pinfunction "1_1") (pintype "passive"))
      (node (ref "R51") (pin "1") (pinfunction "1_1") (pintype "passive"))
      (node (ref "R52") (pin "1") (pinfunction "1_1") (pintype "passive"))
      (node (ref "R53") (pin "1") (pinfunction "1_1") (pintype "passive"))
      (node (ref "R54") (pin "1") (pinfunction "1_1") (pintype "passive"))
      (node (ref "R55") (pin "1") (pinfunction "1_1") (pintype "passive"))
      (node (ref "R56") (pin "1") (pinfunction "1_1") (pintype "passive"))
      (node (ref "R57") (pin "1") (pinfunction "1_1") (pintype "passive"))
      (node (ref "R58") (pin "1") (pinfunction "1_1") (pintype "passive"))
      (node (ref "R59") (pin "2") (pinfunction "2_2") (pintype "passive"))
      (node (ref "R60") (pin "2") (pinfunction "2_2") (pintype "passive"))
      (node (ref "R61") (pin "2") (pinfunction "2_2") (pintype "passive"))
      (node (ref "R62") (pin "2") (pinfunction "2_2") (pintype "passive"))
      (node (ref "R63") (pin "2") (pinfunction "2_2") (pintype "passive"))
      (node (ref "R64") (pin "2") (pinfunction "2_2") (pintype "passive"))
      (node (ref "R65") (pin "2") (pinfunction "2_2") (pintype "passive"))
      (node (ref "R66") (pin "2") (pinfunction "2_2") (pintype "passive"))
      (node (ref "R67") (pin "2") (pinfunction "2_2") (pintype "passive"))
      (node (ref "R68") (pin "2") (pinfunction "2_2") (pintype "passive"))
      (node (ref "R69") (pin "2") (pinfunction "2_2") (pintype "passive"))
      (node (ref "R70") (pin "2") (pinfunction "2_2") (pintype "passive"))
      (node (ref "R71") (pin "2") (pinfunction "2_2") (pintype "passive"))
      (node (ref "SCIENCE") (pin "5V_ICSP") (pinfunction "5V_ICSP_5V_ICSP") (pintype "bidirectional"))
      (node (ref "SCIENCE") (pin "GND1") (pinfunction "GND1_GND1") (pintype "bidirectional"))
      (node (ref "SCIENCE") (pin "GND_1") (pinfunction "GND_1_GND_1") (pintype "bidirectional"))
      (node (ref "SCIENCE") (pin "GND_2") (pinfunction "GND_2_GND_2") (pintype "bidirectional"))
      (node (ref "SCIENCE") (pin "GND_A") (pinfunction "GND_A_GND_A") (pintype "bidirectional"))
      (node (ref "SCIENCE") (pin "GND_B") (pinfunction "GND_B_GND_B") (pintype "bidirectional"))
      (node (ref "SCI_SENSORS") (pin "4") (pinfunction "S_4") (pintype "passive"))
      (node (ref "TX2HEADER") (pin "16") (pinfunction "16_16") (pintype "passive"))
      (node (ref "TX2HEADER") (pin "18") (pinfunction "18_18") (pintype "passive"))
      (node (ref "TX2HEADER") (pin "19") (pinfunction "19_19") (pintype "passive"))
      (node (ref "TX2HEADER") (pin "20") (pinfunction "20_20") (pintype "passive"))
      (node (ref "TX2_POWER") (pin "2") (pinfunction "S_2") (pintype "passive"))
      (node (ref "VIN") (pin "3") (pinfunction "S_3") (pintype "passive"))
      (node (ref "VIN") (pin "4") (pinfunction "S_4") (pintype "passive"))
    )
    (net (code "59") (name "/LIMIT_1") (class "Default")
      (node (ref "ARM") (pin "37") (pinfunction "37_37") (pintype "bidirectional"))
      (node (ref "LIMIT_4") (pin "7") (pinfunction "VO1_7") (pintype "passive"))
    )
    (net (code "60") (name "/LIMIT_2") (class "Default")
      (node (ref "ARM") (pin "38") (pinfunction "38_38") (pintype "bidirectional"))
      (node (ref "LIMIT_4") (pin "6") (pinfunction "VO2_6") (pintype "passive"))
    )
    (net (code "61") (name "/LIMIT_3") (class "Default")
      (node (ref "ARM") (pin "39") (pinfunction "39_39") (pintype "bidirectional"))
      (node (ref "LIMIT_5") (pin "7") (pinfunction "VO1_7") (pintype "passive"))
    )
    (net (code "62") (name "/LIMIT_4") (class "Default")
      (node (ref "ARM") (pin "40") (pinfunction "40_40") (pintype "bidirectional"))
      (node (ref "LIMIT_5") (pin "6") (pinfunction "VO2_6") (pintype "passive"))
    )
    (net (code "63") (name "/LIMIT_5") (class "Default")
      (node (ref "ARM") (pin "41") (pinfunction "41_41") (pintype "bidirectional"))
      (node (ref "LIMIT_6") (pin "7") (pinfunction "VO1_7") (pintype "passive"))
    )
    (net (code "64") (name "/LIM_1") (class "Default")
      (node (ref "LIMIT_SWITCHES") (pin "6") (pinfunction "S_6") (pintype "passive"))
      (node (ref "R25") (pin "1") (pinfunction "1_1") (pintype "passive"))
      (node (ref "R31") (pin "2") (pinfunction "2_2") (pintype "passive"))
    )
    (net (code "65") (name "/LIM_2") (class "Default")
      (node (ref "LIMIT_SWITCHES") (pin "7") (pinfunction "S_7") (pintype "passive"))
      (node (ref "R26") (pin "1") (pinfunction "1_1") (pintype "passive"))
      (node (ref "R32") (pin "2") (pinfunction "2_2") (pintype "passive"))
    )
    (net (code "66") (name "/LIM_3") (class "Default")
      (node (ref "LIMIT_SWITCHES") (pin "8") (pinfunction "S_8") (pintype "passive"))
      (node (ref "R27") (pin "1") (pinfunction "1_1") (pintype "passive"))
      (node (ref "R33") (pin "2") (pinfunction "2_2") (pintype "passive"))
    )
    (net (code "67") (name "/LIM_4") (class "Default")
      (node (ref "LIMIT_SWITCHES") (pin "9") (pinfunction "S_9") (pintype "passive"))
      (node (ref "R28") (pin "1") (pinfunction "1_1") (pintype "passive"))
      (node (ref "R34") (pin "2") (pinfunction "2_2") (pintype "passive"))
    )
    (net (code "68") (name "/LIM_5") (class "Default")
      (node (ref "LIMIT_SWITCHES") (pin "10") (pinfunction "S_10") (pintype "passive"))
      (node (ref "R29") (pin "1") (pinfunction "1_1") (pintype "passive"))
      (node (ref "R35") (pin "2") (pinfunction "2_2") (pintype "passive"))
    )
    (net (code "69") (name "/PWM_ARM_J1") (class "Default")
      (node (ref "ARM") (pin "2") (pinfunction "2_2") (pintype "bidirectional"))
      (node (ref "ARM_PWM") (pin "1") (pinfunction "S_1") (pintype "passive"))
    )
    (net (code "70") (name "/PWM_ARM_J2") (class "Default")
      (node (ref "ARM") (pin "3") (pinfunction "3_3") (pintype "bidirectional"))
      (node (ref "ARM_PWM") (pin "2") (pinfunction "S_2") (pintype "passive"))
    )
    (net (code "71") (name "/PWM_ARM_J3") (class "Default")
      (node (ref "ARM") (pin "4") (pinfunction "4_4") (pintype "bidirectional"))
      (node (ref "ARM_PWM") (pin "3") (pinfunction "S_3") (pintype "passive"))
    )
    (net (code "72") (name "/PWM_ARM_J4") (class "Default")
      (node (ref "ARM") (pin "5") (pinfunction "5_5") (pintype "bidirectional"))
      (node (ref "ARM_PWM") (pin "4") (pinfunction "S_4") (pintype "passive"))
    )
    (net (code "73") (name "/PWM_ARM_J5") (class "Default")
      (node (ref "ARM") (pin "6") (pinfunction "6_6") (pintype "bidirectional"))
      (node (ref "ARM_PWM") (pin "5") (pinfunction "S_5") (pintype "passive"))
    )
    (net (code "74") (name "/PWM_ARM_J6") (class "Default")
      (node (ref "ARM") (pin "7") (pinfunction "7_7") (pintype "bidirectional"))
      (node (ref "ARM_PWM") (pin "6") (pinfunction "S_6") (pintype "passive"))
    )
    (net (code "75") (name "/PWM_DRIVE_1") (class "Default")
      (node (ref "DRIVE") (pin "2") (pinfunction "2_2") (pintype "bidirectional"))
      (node (ref "DRIVE_PWM") (pin "1") (pinfunction "S_1") (pintype "passive"))
    )
    (net (code "76") (name "/PWM_DRIVE_2") (class "Default")
      (node (ref "DRIVE") (pin "3") (pinfunction "3_3") (pintype "bidirectional"))
      (node (ref "DRIVE_PWM") (pin "2") (pinfunction "S_2") (pintype "passive"))
    )
    (net (code "77") (name "/PWM_DRIVE_3") (class "Default")
      (node (ref "DRIVE") (pin "4") (pinfunction "4_4") (pintype "bidirectional"))
      (node (ref "DRIVE_PWM") (pin "3") (pinfunction "S_3") (pintype "passive"))
    )
    (net (code "78") (name "/PWM_DRIVE_4") (class "Default")
      (node (ref "DRIVE") (pin "5") (pinfunction "5_5") (pintype "bidirectional"))
      (node (ref "DRIVE_PWM") (pin "4") (pinfunction "S_4") (pintype "passive"))
    )
    (net (code "79") (name "/PWM_DRIVE_5") (class "Default")
      (node (ref "DRIVE") (pin "6") (pinfunction "6_6") (pintype "bidirectional"))
      (node (ref "DRIVE_PWM") (pin "5") (pinfunction "S_5") (pintype "passive"))
    )
    (net (code "80") (name "/PWM_DRIVE_6") (class "Default")
      (node (ref "DRIVE") (pin "7") (pinfunction "7_7") (pintype "bidirectional"))
      (node (ref "DRIVE_PWM") (pin "6") (pinfunction "S_6") (pintype "passive"))
    )
    (net (code "81") (name "/RESET") (class "Default")
      (node (ref "ARM") (pin "RESET") (pinfunction "RESET_RESET") (pintype "bidirectional"))
      (node (ref "DRIVE") (pin "RESET") (pinfunction "RESET_RESET") (pintype "bidirectional"))
      (node (ref "R59") (pin "1") (pinfunction "1_1") (pintype "passive"))
      (node (ref "S4") (pin "1") (pinfunction "S_1") (pintype "passive"))
      (node (ref "SCIENCE") (pin "RESET") (pinfunction "RESET_RESET") (pintype "bidirectional"))
      (node (ref "TX2HEADER") (pin "15") (pinfunction "15_15") (pintype "passive"))
    )
    (net (code "82") (name "/SCI_ADD_1") (class "Default")
      (node (ref "R68") (pin "1") (pinfunction "1_1") (pintype "passive"))
      (node (ref "SCIENCE") (pin "42") (pinfunction "42_42") (pintype "bidirectional"))
      (node (ref "SCI_ADD") (pin "8") (pinfunction "8_8") (pintype "passive"))
    )
    (net (code "83") (name "/SCI_ADD_2") (class "Default")
      (node (ref "R69") (pin "1") (pinfunction "1_1") (pintype "passive"))
      (node (ref "SCIENCE") (pin "43") (pinfunction "43_43") (pintype "bidirectional"))
      (node (ref "SCI_ADD") (pin "7") (pinfunction "7_7") (pintype "passive"))
    )
    (net (code "84") (name "/SCI_ADD_3") (class "Default")
      (node (ref "R70") (pin "1") (pinfunction "1_1") (pintype "passive"))
      (node (ref "SCIENCE") (pin "44") (pinfunction "44_44") (pintype "bidirectional"))
      (node (ref "SCI_ADD") (pin "6") (pinfunction "6_6") (pintype "passive"))
    )
    (net (code "85") (name "/SCI_ADD_4") (class "Default")
      (node (ref "R71") (pin "1") (pinfunction "1_1") (pintype "passive"))
      (node (ref "SCIENCE") (pin "45") (pinfunction "45_45") (pintype "bidirectional"))
      (node (ref "SCI_ADD") (pin "5") (pinfunction "5_5") (pintype "passive"))
    )
    (net (code "86") (name "/SCL") (class "Default")
      (node (ref "ARM") (pin "SCL") (pinfunction "SCL_SCL") (pintype "bidirectional"))
      (node (ref "DRIVE") (pin "SCL") (pinfunction "SCL_SCL") (pintype "bidirectional"))
      (node (ref "IMU1") (pin "2") (pinfunction "S_2") (pintype "passive"))
      (node (ref "IMU2") (pin "2") (pinfunction "S_2") (pintype "passive"))
      (node (ref "SCIENCE") (pin "SCL") (pinfunction "SCL_SCL") (pintype "bidirectional"))
      (node (ref "TX2HEADER") (pin "11") (pinfunction "11_11") (pintype "passive"))
    )
    (net (code "87") (name "/SDA") (class "Default")
      (node (ref "ARM") (pin "SDA") (pinfunction "SDA_SDA") (pintype "bidirectional"))
      (node (ref "DRIVE") (pin "SDA") (pinfunction "SDA_SDA") (pintype "bidirectional"))
      (node (ref "IMU1") (pin "1") (pinfunction "S_1") (pintype "passive"))
      (node (ref "IMU2") (pin "1") (pinfunction "S_1") (pintype "passive"))
      (node (ref "SCIENCE") (pin "SDA") (pinfunction "SDA_SDA") (pintype "bidirectional"))
      (node (ref "TX2HEADER") (pin "12") (pinfunction "12_12") (pintype "passive"))
    )
    (net (code "88") (name "/STEPPER_DIR") (class "Default")
      (node (ref "ARM") (pin "35") (pinfunction "35_35") (pintype "bidirectional"))
      (node (ref "ARM_STEPPER") (pin "2") (pinfunction "S_2") (pintype "passive"))
    )
    (net (code "89") (name "/STEPPER_ENA") (class "Default")
      (node (ref "ARM") (pin "34") (pinfunction "34_34") (pintype "bidirectional"))
      (node (ref "ARM_STEPPER") (pin "1") (pinfunction "S_1") (pintype "passive"))
    )
    (net (code "90") (name "/STEPPER_PUL") (class "Default")
      (node (ref "ARM") (pin "36") (pinfunction "36_36") (pintype "bidirectional"))
      (node (ref "ARM_STEPPER") (pin "3") (pinfunction "S_3") (pintype "passive"))
    )
    (net (code "91") (name "/UART0_RX") (class "Default")
      (node (ref "GPS") (pin "1") (pinfunction "S_1") (pintype "passive"))
      (node (ref "TX2HEADER") (pin "4") (pinfunction "4_4") (pintype "passive"))
    )
    (net (code "92") (name "/UART0_TX") (class "Default")
      (node (ref "GPS") (pin "2") (pinfunction "S_2") (pintype "passive"))
      (node (ref "TX2HEADER") (pin "3") (pinfunction "3_3") (pintype "passive"))
    )
    (net (code "93") (name "/UART1_RX") (class "Default")
      (node (ref "TX2HEADER") (pin "6") (pinfunction "6_6") (pintype "passive"))
    )
    (net (code "94") (name "/UART1_TX") (class "Default")
      (node (ref "TX2HEADER") (pin "5") (pinfunction "5_5") (pintype "passive"))
    )
    (net (code "95") (name "/VCC") (class "Default")
      (node (ref "ARM") (pin "VIN") (pinfunction "VIN_VIN") (pintype "bidirectional"))
      (node (ref "ARM_ADD") (pin "1") (pinfunction "1_1") (pintype "passive"))
      (node (ref "ARM_ADD") (pin "2") (pinfunction "2_2") (pintype "passive"))
      (node (ref "ARM_ADD") (pin "3") (pinfunction "3_3") (pintype "passive"))
      (node (ref "ARM_ADD") (pin "4") (pinfunction "4_4") (pintype "passive"))
      (node (ref "ARM_ENCODERS") (pin "13") (pinfunction "S_13") (pintype "passive"))
      (node (ref "ARM_ENCODERS") (pin "14") (pinfunction "S_14") (pintype "passive"))
      (node (ref "ARM_ENCODERS") (pin "15") (pinfunction "S_15") (pintype "passive"))
      (node (ref "ARM_ENCODERS") (pin "16") (pinfunction "S_16") (pintype "passive"))
      (node (ref "ARM_ENCODERS") (pin "17") (pinfunction "S_17") (pintype "passive"))
      (node (ref "ARM_ENCODERS") (pin "18") (pinfunction "S_18") (pintype "passive"))
      (node (ref "ARM_STEPPER") (pin "4") (pinfunction "S_4") (pintype "passive"))
      (node (ref "ARM_STEPPER") (pin "5") (pinfunction "S_5") (pintype "passive"))
      (node (ref "ARM_STEPPER") (pin "6") (pinfunction "S_6") (pintype "passive"))
      (node (ref "C10") (pin "1") (pinfunction "1_1") (pintype "passive"))
      (node (ref "C11") (pin "1") (pinfunction "1_1") (pintype "passive"))
      (node (ref "C12") (pin "1") (pinfunction "1_1") (pintype "passive"))
      (node (ref "C13") (pin "1") (pinfunction "1_1") (pintype "passive"))
      (node (ref "C14") (pin "1") (pinfunction "1_1") (pintype "passive"))
      (node (ref "C15") (pin "1") (pinfunction "1_1") (pintype "passive"))
      (node (ref "C16") (pin "1") (pinfunction "1_1") (pintype "passive"))
      (node (ref "C17") (pin "1") (pinfunction "1_1") (pintype "passive"))
      (node (ref "C18") (pin "1") (pinfunction "1_1") (pintype "passive"))
      (node (ref "C19") (pin "1") (pinfunction "1_1") (pintype "passive"))
      (node (ref "C3") (pin "1") (pinfunction "1_1") (pintype "passive"))
      (node (ref "C4") (pin "2") (pinfunction "2_2") (pintype "passive"))
      (node (ref "C5") (pin "+") (pinfunction "+_+") (pintype "passive"))
      (node (ref "C6") (pin "1") (pinfunction "1_1") (pintype "passive"))
      (node (ref "C7") (pin "1") (pinfunction "1_1") (pintype "passive"))
      (node (ref "C8") (pin "1") (pinfunction "1_1") (pintype "passive"))
      (node (ref "C9") (pin "1") (pinfunction "1_1") (pintype "passive"))
      (node (ref "DRIVE") (pin "VIN") (pinfunction "VIN_VIN") (pintype "bidirectional"))
      (node (ref "DRIVE_ADD") (pin "1") (pinfunction "1_1") (pintype "passive"))
      (node (ref "DRIVE_ADD") (pin "2") (pinfunction "2_2") (pintype "passive"))
      (node (ref "DRIVE_ADD") (pin "3") (pinfunction "3_3") (pintype "passive"))
      (node (ref "DRIVE_ADD") (pin "4") (pinfunction "4_4") (pintype "passive"))
      (node (ref "DRIVE_ENCODERS") (pin "13") (pinfunction "S_13") (pintype "passive"))
      (node (ref "DRIVE_ENCODERS") (pin "14") (pinfunction "S_14") (pintype "passive"))
      (node (ref "DRIVE_ENCODERS") (pin "15") (pinfunction "S_15") (pintype "passive"))
      (node (ref "DRIVE_ENCODERS") (pin "16") (pinfunction "S_16") (pintype "passive"))
      (node (ref "DRIVE_ENCODERS") (pin "17") (pinfunction "S_17") (pintype "passive"))
      (node (ref "DRIVE_ENCODERS") (pin "18") (pinfunction "S_18") (pintype "passive"))
      (node (ref "ENC1") (pin "8") (pinfunction "VCC_8") (pintype "passive"))
      (node (ref "ENC10") (pin "8") (pinfunction "VCC_8") (pintype "passive"))
      (node (ref "ENC11") (pin "8") (pinfunction "VCC_8") (pintype "passive"))
      (node (ref "ENC12") (pin "8") (pinfunction "VCC_8") (pintype "passive"))
      (node (ref "ENC2") (pin "8") (pinfunction "VCC_8") (pintype "passive"))
      (node (ref "ENC3") (pin "8") (pinfunction "VCC_8") (pintype "passive"))
      (node (ref "ENC4") (pin "8") (pinfunction "VCC_8") (pintype "passive"))
      (node (ref "ENC5") (pin "8") (pinfunction "VCC_8") (pintype "passive"))
      (node (ref "ENC6") (pin "8") (pinfunction "VCC_8") (pintype "passive"))
      (node (ref "ENC7") (pin "8") (pinfunction "VCC_8") (pintype "passive"))
      (node (ref "ENC8") (pin "8") (pinfunction "VCC_8") (pintype "passive"))
      (node (ref "ENC9") (pin "8") (pinfunction "VCC_8") (pintype "passive"))
      (node (ref "LIMIT_4") (pin "8") (pinfunction "VCC_8") (pintype "passive"))
      (node (ref "LIMIT_5") (pin "8") (pinfunction "VCC_8") (pintype "passive"))
      (node (ref "LIMIT_6") (pin "8") (pinfunction "VCC_8") (pintype "passive"))
      (node (ref "LIMIT_SWITCHES") (pin "1") (pinfunction "S_1") (pintype "passive"))
      (node (ref "LIMIT_SWITCHES") (pin "2") (pinfunction "S_2") (pintype "passive"))
      (node (ref "LIMIT_SWITCHES") (pin "3") (pinfunction "S_3") (pintype "passive"))
      (node (ref "LIMIT_SWITCHES") (pin "4") (pinfunction "S_4") (pintype "passive"))
      (node (ref "LIMIT_SWITCHES") (pin "5") (pinfunction "S_5") (pintype "passive"))
      (node (ref "S4") (pin "3") (pinfunction "P_3") (pintype "passive"))
      (node (ref "SCIENCE") (pin "VIN") (pinfunction "VIN_VIN") (pintype "bidirectional"))
      (node (ref "SCI_ADD") (pin "1") (pinfunction "1_1") (pintype "passive"))
      (node (ref "SCI_ADD") (pin "2") (pinfunction "2_2") (pintype "passive"))
      (node (ref "SCI_ADD") (pin "3") (pinfunction "3_3") (pintype "passive"))
      (node (ref "SCI_ADD") (pin "4") (pinfunction "4_4") (pintype "passive"))
      (node (ref "VIN") (pin "2") (pinfunction "S_2") (pintype "passive"))
    )
    (net (code "96") (name "/VDD") (class "Default")
      (node (ref "GPS") (pin "3") (pinfunction "S_3") (pintype "passive"))
      (node (ref "IMU1") (pin "3") (pinfunction "S_3") (pintype "passive"))
      (node (ref "IMU2") (pin "3") (pinfunction "S_3") (pintype "passive"))
      (node (ref "SCI_SENSORS") (pin "3") (pinfunction "S_3") (pintype "passive"))
      (node (ref "TX2HEADER") (pin "1") (pinfunction "1_1") (pintype "passive"))
    )
    (net (code "97") (name "Net-(ARM_PWMB-S)") (class "Default")
      (node (ref "ARM_PWM") (pin "10") (pinfunction "S_10") (pintype "passive"))
      (node (ref "ARM_PWM") (pin "11") (pinfunction "S_11") (pintype "passive"))
      (node (ref "ARM_PWM") (pin "12") (pinfunction "S_12") (pintype "passive"))
      (node (ref "ARM_PWM") (pin "7") (pinfunction "S_7") (pintype "passive"))
      (node (ref "ARM_PWM") (pin "8") (pinfunction "S_8") (pintype "passive"))
      (node (ref "ARM_PWM") (pin "9") (pinfunction "S_9") (pintype "passive"))
    )
    (net (code "98") (name "Net-(DRIVE_PWMB-S)") (class "Default")
      (node (ref "DRIVE_PWM") (pin "10") (pinfunction "S_10") (pintype "passive"))
      (node (ref "DRIVE_PWM") (pin "11") (pinfunction "S_11") (pintype "passive"))
      (node (ref "DRIVE_PWM") (pin "12") (pinfunction "S_12") (pintype "passive"))
      (node (ref "DRIVE_PWM") (pin "7") (pinfunction "S_7") (pintype "passive"))
      (node (ref "DRIVE_PWM") (pin "8") (pinfunction "S_8") (pintype "passive"))
      (node (ref "DRIVE_PWM") (pin "9") (pinfunction "S_9") (pintype "passive"))
    )
    (net (code "99") (name "Net-(ENC1A-A1)") (class "Default")
      (node (ref "ENC1") (pin "1") (pinfunction "A1_1") (pintype "passive"))
      (node (ref "R1") (pin "2") (pinfunction "2_2") (pintype "passive"))
    )
    (net (code "100") (name "Net-(ENC1B-A2)") (class "Default")
      (node (ref "ENC1") (pin "4") (pinfunction "A2_4") (pintype "passive"))
      (node (ref "R2") (pin "2") (pinfunction "2_2") (pintype "passive"))
    )
    (net (code "101") (name "Net-(ENC2A-A1)") (class "Default")
      (node (ref "ENC2") (pin "1") (pinfunction "A1_1") (pintype "passive"))
      (node (ref "R3") (pin "2") (pinfunction "2_2") (pintype "passive"))
    )
    (net (code "102") (name "Net-(ENC2B-A2)") (class "Default")
      (node (ref "ENC2") (pin "4") (pinfunction "A2_4") (pintype "passive"))
      (node (ref "R4") (pin "2") (pinfunction "2_2") (pintype "passive"))
    )
    (net (code "103") (name "Net-(ENC3A-A1)") (class "Default")
      (node (ref "ENC3") (pin "1") (pinfunction "A1_1") (pintype "passive"))
      (node (ref "R5") (pin "2") (pinfunction "2_2") (pintype "passive"))
    )
    (net (code "104") (name "Net-(ENC3B-A2)") (class "Default")
      (node (ref "ENC3") (pin "4") (pinfunction "A2_4") (pintype "passive"))
      (node (ref "R6") (pin "2") (pinfunction "2_2") (pintype "passive"))
    )
    (net (code "105") (name "Net-(ENC4A-A1)") (class "Default")
      (node (ref "ENC4") (pin "1") (pinfunction "A1_1") (pintype "passive"))
      (node (ref "R7") (pin "2") (pinfunction "2_2") (pintype "passive"))
    )
    (net (code "106") (name "Net-(ENC4B-A2)") (class "Default")
      (node (ref "ENC4") (pin "4") (pinfunction "A2_4") (pintype "passive"))
      (node (ref "R8") (pin "2") (pinfunction "2_2") (pintype "passive"))
    )
    (net (code "107") (name "Net-(ENC5A-A1)") (class "Default")
      (node (ref "ENC5") (pin "1") (pinfunction "A1_1") (pintype "passive"))
      (node (ref "R9") (pin "2") (pinfunction "2_2") (pintype "passive"))
    )
    (net (code "108") (name "Net-(ENC5B-A2)") (class "Default")
      (node (ref "ENC5") (pin "4") (pinfunction "A2_4") (pintype "passive"))
      (node (ref "R10") (pin "2") (pinfunction "2_2") (pintype "passive"))
    )
    (net (code "109") (name "Net-(ENC6A-A1)") (class "Default")
      (node (ref "ENC6") (pin "1") (pinfunction "A1_1") (pintype "passive"))
      (node (ref "R11") (pin "2") (pinfunction "2_2") (pintype "passive"))
    )
    (net (code "110") (name "Net-(ENC6B-A2)") (class "Default")
      (node (ref "ENC6") (pin "4") (pinfunction "A2_4") (pintype "passive"))
      (node (ref "R12") (pin "2") (pinfunction "2_2") (pintype "passive"))
    )
    (net (code "111") (name "Net-(ENC7A-A1)") (class "Default")
      (node (ref "ENC7") (pin "1") (pinfunction "A1_1") (pintype "passive"))
      (node (ref "R13") (pin "2") (pinfunction "2_2") (pintype "passive"))
    )
    (net (code "112") (name "Net-(ENC7B-A2)") (class "Default")
      (node (ref "ENC7") (pin "4") (pinfunction "A2_4") (pintype "passive"))
      (node (ref "R14") (pin "2") (pinfunction "2_2") (pintype "passive"))
    )
    (net (code "113") (name "Net-(ENC8A-A1)") (class "Default")
      (node (ref "ENC8") (pin "1") (pinfunction "A1_1") (pintype "passive"))
      (node (ref "R15") (pin "2") (pinfunction "2_2") (pintype "passive"))
    )
    (net (code "114") (name "Net-(ENC8B-A2)") (class "Default")
      (node (ref "ENC8") (pin "4") (pinfunction "A2_4") (pintype "passive"))
      (node (ref "R16") (pin "2") (pinfunction "2_2") (pintype "passive"))
    )
    (net (code "115") (name "Net-(ENC9A-A1)") (class "Default")
      (node (ref "ENC9") (pin "1") (pinfunction "A1_1") (pintype "passive"))
      (node (ref "R17") (pin "2") (pinfunction "2_2") (pintype "passive"))
    )
    (net (code "116") (name "Net-(ENC9B-A2)") (class "Default")
      (node (ref "ENC9") (pin "4") (pinfunction "A2_4") (pintype "passive"))
      (node (ref "R18") (pin "2") (pinfunction "2_2") (pintype "passive"))
    )
    (net (code "117") (name "Net-(ENC10A-A1)") (class "Default")
      (node (ref "ENC10") (pin "1") (pinfunction "A1_1") (pintype "passive"))
      (node (ref "R19") (pin "2") (pinfunction "2_2") (pintype "passive"))
    )
    (net (code "118") (name "Net-(ENC10B-A2)") (class "Default")
      (node (ref "ENC10") (pin "4") (pinfunction "A2_4") (pintype "passive"))
      (node (ref "R20") (pin "2") (pinfunction "2_2") (pintype "passive"))
    )
    (net (code "119") (name "Net-(ENC11A-A1)") (class "Default")
      (node (ref "ENC11") (pin "1") (pinfunction "A1_1") (pintype "passive"))
      (node (ref "R21") (pin "2") (pinfunction "2_2") (pintype "passive"))
    )
    (net (code "120") (name "Net-(ENC11B-A2)") (class "Default")
      (node (ref "ENC11") (pin "4") (pinfunction "A2_4") (pintype "passive"))
      (node (ref "R22") (pin "2") (pinfunction "2_2") (pintype "passive"))
    )
    (net (code "121") (name "Net-(ENC12A-A1)") (class "Default")
      (node (ref "ENC12") (pin "1") (pinfunction "A1_1") (pintype "passive"))
      (node (ref "R23") (pin "2") (pinfunction "2_2") (pintype "passive"))
    )
    (net (code "122") (name "Net-(ENC12B-A2)") (class "Default")
      (node (ref "ENC12") (pin "4") (pinfunction "A2_4") (pintype "passive"))
      (node (ref "R24") (pin "2") (pinfunction "2_2") (pintype "passive"))
    )
    (net (code "123") (name "Net-(LIMIT_4A-A1)") (class "Default")
      (node (ref "LIMIT_4") (pin "1") (pinfunction "A1_1") (pintype "passive"))
      (node (ref "R25") (pin "2") (pinfunction "2_2") (pintype "passive"))
    )
    (net (code "124") (name "Net-(LIMIT_4B-A2)") (class "Default")
      (node (ref "LIMIT_4") (pin "4") (pinfunction "A2_4") (pintype "passive"))
      (node (ref "R26") (pin "2") (pinfunction "2_2") (pintype "passive"))
    )
    (net (code "125") (name "Net-(LIMIT_5A-A1)") (class "Default")
      (node (ref "LIMIT_5") (pin "1") (pinfunction "A1_1") (pintype "passive"))
      (node (ref "R27") (pin "2") (pinfunction "2_2") (pintype "passive"))
    )
    (net (code "126") (name "Net-(LIMIT_5B-A2)") (class "Default")
      (node (ref "LIMIT_5") (pin "4") (pinfunction "A2_4") (pintype "passive"))
      (node (ref "R28") (pin "2") (pinfunction "2_2") (pintype "passive"))
    )
    (net (code "127") (name "Net-(LIMIT_6A-A1)") (class "Default")
      (node (ref "LIMIT_6") (pin "1") (pinfunction "A1_1") (pintype "passive"))
      (node (ref "R29") (pin "2") (pinfunction "2_2") (pintype "passive"))
    )
    (net (code "128") (name "Net-(SCI_SENSORSA-S)") (class "Default")
      (node (ref "SCIENCE") (pin "SCL1") (pinfunction "SCL1_SCL1") (pintype "bidirectional"))
      (node (ref "SCI_SENSORS") (pin "1") (pinfunction "S_1") (pintype "passive"))
    )
    (net (code "129") (name "Net-(SCI_SENSORSB-S)") (class "Default")
      (node (ref "SCIENCE") (pin "SDA1") (pinfunction "SDA1_SDA1") (pintype "bidirectional"))
      (node (ref "SCI_SENSORS") (pin "2") (pinfunction "S_2") (pintype "passive"))
    )
    (net (code "130") (name "unconnected-(ARM-Pad3V3)") (class "Default")
      (node (ref "ARM") (pin "3V3") (pinfunction "3V3_3V3") (pintype "bidirectional"))
    )
    (net (code "131") (name "unconnected-(ARM-Pad5V)") (class "Default")
      (node (ref "ARM") (pin "5V") (pinfunction "5V_5V") (pintype "bidirectional"))
    )
    (net (code "132") (name "unconnected-(ARM-Pad5V_A)") (class "Default")
      (node (ref "ARM") (pin "5V_A") (pinfunction "5V_A_5V_A") (pintype "bidirectional"))
    )
    (net (code "133") (name "unconnected-(ARM-Pad5V_B)") (class "Default")
      (node (ref "ARM") (pin "5V_B") (pinfunction "5V_B_5V_B") (pintype "bidirectional"))
    )
    (net (code "134") (name "unconnected-(ARM-Pad8)") (class "Default")
      (node (ref "ARM") (pin "8") (pinfunction "8_8") (pintype "bidirectional"))
    )
    (net (code "135") (name "unconnected-(ARM-Pad9)") (class "Default")
      (node (ref "ARM") (pin "9") (pinfunction "9_9") (pintype "bidirectional"))
    )
    (net (code "136") (name "unconnected-(ARM-Pad10)") (class "Default")
      (node (ref "ARM") (pin "10") (pinfunction "10_10") (pintype "bidirectional"))
    )
    (net (code "137") (name "unconnected-(ARM-Pad11)") (class "Default")
      (node (ref "ARM") (pin "11") (pinfunction "11_11") (pintype "bidirectional"))
    )
    (net (code "138") (name "unconnected-(ARM-Pad12)") (class "Default")
      (node (ref "ARM") (pin "12") (pinfunction "12_12") (pintype "bidirectional"))
    )
    (net (code "139") (name "unconnected-(ARM-Pad13)") (class "Default")
      (node (ref "ARM") (pin "13") (pinfunction "13_13") (pintype "bidirectional"))
    )
    (net (code "140") (name "unconnected-(ARM-Pad46)") (class "Default")
      (node (ref "ARM") (pin "46") (pinfunction "46_46") (pintype "bidirectional"))
    )
    (net (code "141") (name "unconnected-(ARM-Pad47)") (class "Default")
      (node (ref "ARM") (pin "47") (pinfunction "47_47") (pintype "bidirectional"))
    )
    (net (code "142") (name "unconnected-(ARM-Pad48)") (class "Default")
      (node (ref "ARM") (pin "48") (pinfunction "48_48") (pintype "bidirectional"))
    )
    (net (code "143") (name "unconnected-(ARM-Pad49)") (class "Default")
      (node (ref "ARM") (pin "49") (pinfunction "49_49") (pintype "bidirectional"))
    )
    (net (code "144") (name "unconnected-(ARM-Pad50)") (class "Default")
      (node (ref "ARM") (pin "50") (pinfunction "50_50") (pintype "bidirectional"))
    )
    (net (code "145") (name "unconnected-(ARM-Pad51)") (class "Default")
      (node (ref "ARM") (pin "51") (pinfunction "51_51") (pintype "bidirectional"))
    )
    (net (code "146") (name "unconnected-(ARM-Pad52)") (class "Default")
      (node (ref "ARM") (pin "52") (pinfunction "52_52") (pintype "bidirectional"))
    )
    (net (code "147") (name "unconnected-(ARM-Pad53)") (class "Default")
      (node (ref "ARM") (pin "53") (pinfunction "53_53") (pintype "bidirectional"))
    )
    (net (code "148") (name "unconnected-(ARM-PadA0)") (class "Default")
      (node (ref "ARM") (pin "A0") (pinfunction "A0_A0") (pintype "bidirectional"))
    )
    (net (code "149") (name "unconnected-(ARM-PadA1)") (class "Default")
      (node (ref "ARM") (pin "A1") (pinfunction "A1_A1") (pintype "bidirectional"))
    )
    (net (code "150") (name "unconnected-(ARM-PadA2)") (class "Default")
      (node (ref "ARM") (pin "A2") (pinfunction "A2_A2") (pintype "bidirectional"))
    )
    (net (code "151") (name "unconnected-(ARM-PadA3)") (class "Default")
      (node (ref "ARM") (pin "A3") (pinfunction "A3_A3") (pintype "bidirectional"))
    )
    (net (code "152") (name "unconnected-(ARM-PadA4)") (class "Default")
      (node (ref "ARM") (pin "A4") (pinfunction "A4_A4") (pintype "bidirectional"))
    )
    (net (code "153") (name "unconnected-(ARM-PadA5)") (class "Default")
      (node (ref "ARM") (pin "A5") (pinfunction "A5_A5") (pintype "bidirectional"))
    )
    (net (code "154") (name "unconnected-(ARM-PadA6)") (class "Default")
      (node (ref "ARM") (pin "A6") (pinfunction "A6_A6") (pintype "bidirectional"))
    )
    (net (code "155") (name "unconnected-(ARM-PadA7)") (class "Default")
      (node (ref "ARM") (pin "A7") (pinfunction "A7_A7") (pintype "bidirectional"))
    )
    (net (code "156") (name "unconnected-(ARM-PadA8)") (class "Default")
      (node (ref "ARM") (pin "A8") (pinfunction "A8_A8") (pintype "bidirectional"))
    )
    (net (code "157") (name "unconnected-(ARM-PadA9)") (class "Default")
      (node (ref "ARM") (pin "A9") (pinfunction "A9_A9") (pintype "bidirectional"))
    )
    (net (code "158") (name "unconnected-(ARM-PadA10)") (class "Default")
      (node (ref "ARM") (pin "A10") (pinfunction "A10_A10") (pintype "bidirectional"))
    )
    (net (code "159") (name "unconnected-(ARM-PadA11)") (class "Default")
      (node (ref "ARM") (pin "A11") (pinfunction "A11_A11") (pintype "bidirectional"))
    )
    (net (code "160") (name "unconnected-(ARM-PadAREF)") (class "Default")
      (node (ref "ARM") (pin "AREF") (pinfunction "AREF_AREF") (pintype "bidirectional"))
    )
    (net (code "161") (name "unconnected-(ARM-PadCANRX)") (class "Default")
      (node (ref "ARM") (pin "CANRX") (pinfunction "CANRX_CANRX") (pintype "bidirectional"))
    )
    (net (code "162") (name "unconnected-(ARM-PadCANTX)") (class "Default")
      (node (ref "ARM") (pin "CANTX") (pinfunction "CANTX_CANTX") (pintype "bidirectional"))
    )
    (net (code "163") (name "unconnected-(ARM-PadDAC0)") (class "Default")
      (node (ref "ARM") (pin "DAC0") (pinfunction "DAC0_DAC0") (pintype "bidirectional"))
    )
    (net (code "164") (name "unconnected-(ARM-PadDAC1)") (class "Default")
      (node (ref "ARM") (pin "DAC1") (pinfunction "DAC1_DAC1") (pintype "bidirectional"))
    )
    (net (code "165") (name "unconnected-(ARM-PadGND_DEBUG)") (class "Default")
      (node (ref "ARM") (pin "GND_DEBUG") (pinfunction "GND_DEBUG_GND_DEBUG") (pintype "bidirectional"))
    )
    (net (code "166") (name "unconnected-(ARM-PadGND_ICSP)") (class "Default")
      (node (ref "ARM") (pin "GND_ICSP") (pinfunction "GND_ICSP_GND_ICSP") (pintype "bidirectional"))
    )
    (net (code "167") (name "unconnected-(ARM-PadIOREF)") (class "Default")
      (node (ref "ARM") (pin "IOREF") (pinfunction "IOREF_IOREF") (pintype "bidirectional"))
    )
    (net (code "168") (name "unconnected-(ARM-PadMISO_ICSP)") (class "Default")
      (node (ref "ARM") (pin "MISO_ICSP") (pinfunction "MISO_ICSP_MISO_ICSP") (pintype "bidirectional"))
    )
    (net (code "169") (name "unconnected-(ARM-PadMOSI_ICSP)") (class "Default")
      (node (ref "ARM") (pin "MOSI_ICSP") (pinfunction "MOSI_ICSP_MOSI_ICSP") (pintype "bidirectional"))
    )
    (net (code "170") (name "unconnected-(ARM-PadNC)") (class "Default")
      (node (ref "ARM") (pin "NC") (pinfunction "NC_NC") (pintype "bidirectional"))
    )
    (net (code "171") (name "unconnected-(ARM-PadRESET_DEBUG)") (class "Default")
      (node (ref "ARM") (pin "RESET_DEBUG") (pinfunction "RESET_DEBUG_RESET_DEBUG") (pintype "bidirectional"))
    )
    (net (code "172") (name "unconnected-(ARM-PadRESET_ICSP)") (class "Default")
      (node (ref "ARM") (pin "RESET_ICSP") (pinfunction "RESET_ICSP_RESET_ICSP") (pintype "bidirectional"))
    )
    (net (code "173") (name "unconnected-(ARM-PadRX0)") (class "Default")
      (node (ref "ARM") (pin "RX0") (pinfunction "RX0_RX0") (pintype "bidirectional"))
    )
    (net (code "174") (name "unconnected-(ARM-PadRX1)") (class "Default")
      (node (ref "ARM") (pin "RX1") (pinfunction "RX1_RX1") (pintype "bidirectional"))
    )
    (net (code "175") (name "unconnected-(ARM-PadRX2)") (class "Default")
      (node (ref "ARM") (pin "RX2") (pinfunction "RX2_RX2") (pintype "bidirectional"))
    )
    (net (code "176") (name "unconnected-(ARM-PadRX3)") (class "Default")
      (node (ref "ARM") (pin "RX3") (pinfunction "RX3_RX3") (pintype "bidirectional"))
    )
    (net (code "177") (name "unconnected-(ARM-PadSCK_ICSP)") (class "Default")
      (node (ref "ARM") (pin "SCK_ICSP") (pinfunction "SCK_ICSP_SCK_ICSP") (pintype "bidirectional"))
    )
    (net (code "178") (name "unconnected-(ARM-PadSCL1)") (class "Default")
      (node (ref "ARM") (pin "SCL1") (pinfunction "SCL1_SCL1") (pintype "bidirectional"))
    )
    (net (code "179") (name "unconnected-(ARM-PadSDA1)") (class "Default")
      (node (ref "ARM") (pin "SDA1") (pinfunction "SDA1_SDA1") (pintype "bidirectional"))
    )
    (net (code "180") (name "unconnected-(ARM-PadSWCLK_DEBUG)") (class "Default")
      (node (ref "ARM") (pin "SWCLK_DEBUG") (pinfunction "SWCLK_DEBUG_SWCLK_DEBUG") (pintype "bidirectional"))
    )
    (net (code "181") (name "unconnected-(ARM-PadSWDIO_DEBUG)") (class "Default")
      (node (ref "ARM") (pin "SWDIO_DEBUG") (pinfunction "SWDIO_DEBUG_SWDIO_DEBUG") (pintype "bidirectional"))
    )
    (net (code "182") (name "unconnected-(ARM-PadTX0)") (class "Default")
      (node (ref "ARM") (pin "TX0") (pinfunction "TX0_TX0") (pintype "bidirectional"))
    )
    (net (code "183") (name "unconnected-(ARM-PadTX1)") (class "Default")
      (node (ref "ARM") (pin "TX1") (pinfunction "TX1_TX1") (pintype "bidirectional"))
    )
    (net (code "184") (name "unconnected-(ARM-PadTX2)") (class "Default")
      (node (ref "ARM") (pin "TX2") (pinfunction "TX2_TX2") (pintype "bidirectional"))
    )
    (net (code "185") (name "unconnected-(ARM-PadTX3)") (class "Default")
      (node (ref "ARM") (pin "TX3") (pinfunction "TX3_TX3") (pintype "bidirectional"))
    )
    (net (code "186") (name "unconnected-(DRIVE-Pad3V3)") (class "Default")
      (node (ref "DRIVE") (pin "3V3") (pinfunction "3V3_3V3") (pintype "bidirectional"))
    )
    (net (code "187") (name "unconnected-(DRIVE-Pad5V)") (class "Default")
      (node (ref "DRIVE") (pin "5V") (pinfunction "5V_5V") (pintype "bidirectional"))
    )
    (net (code "188") (name "unconnected-(DRIVE-Pad5V_A)") (class "Default")
      (node (ref "DRIVE") (pin "5V_A") (pinfunction "5V_A_5V_A") (pintype "bidirectional"))
    )
    (net (code "189") (name "unconnected-(DRIVE-Pad5V_B)") (class "Default")
      (node (ref "DRIVE") (pin "5V_B") (pinfunction "5V_B_5V_B") (pintype "bidirectional"))
    )
    (net (code "190") (name "unconnected-(DRIVE-Pad8)") (class "Default")
      (node (ref "DRIVE") (pin "8") (pinfunction "8_8") (pintype "bidirectional"))
    )
    (net (code "191") (name "unconnected-(DRIVE-Pad9)") (class "Default")
      (node (ref "DRIVE") (pin "9") (pinfunction "9_9") (pintype "bidirectional"))
    )
    (net (code "192") (name "unconnected-(DRIVE-Pad10)") (class "Default")
      (node (ref "DRIVE") (pin "10") (pinfunction "10_10") (pintype "bidirectional"))
    )
    (net (code "193") (name "unconnected-(DRIVE-Pad11)") (class "Default")
      (node (ref "DRIVE") (pin "11") (pinfunction "11_11") (pintype "bidirectional"))
    )
    (net (code "194") (name "unconnected-(DRIVE-Pad12)") (class "Default")
      (node (ref "DRIVE") (pin "12") (pinfunction "12_12") (pintype "bidirectional"))
    )
    (net (code "195") (name "unconnected-(DRIVE-Pad13)") (class "Default")
      (node (ref "DRIVE") (pin "13") (pinfunction "13_13") (pintype "bidirectional"))
    )
    (net (code "196") (name "unconnected-(DRIVE-Pad34)") (class "Default")
      (node (ref "DRIVE") (pin "34") (pinfunction "34_34") (pintype "bidirectional"))
    )
    (net (code "197") (name "unconnected-(DRIVE-Pad35)") (class "Default")
      (node (ref "DRIVE") (pin "35") (pinfunction "35_35") (pintype "bidirectional"))
    )
    (net (code "198") (name "unconnected-(DRIVE-Pad36)") (class "Default")
      (node (ref "DRIVE") (pin "36") (pinfunction "36_36") (pintype "bidirectional"))
    )
    (net (code "199") (name "unconnected-(DRIVE-Pad37)") (class "Default")
      (node (ref "DRIVE") (pin "37") (pinfunction "37_37") (pintype "bidirectional"))
    )
    (net (code "200") (name "unconnected-(DRIVE-Pad38)") (class "Default")
      (node (ref "DRIVE") (pin "38") (pinfunction "38_38") (pintype "bidirectional"))
    )
    (net (code "201") (name "unconnected-(DRIVE-Pad39)") (class "Default")
      (node (ref "DRIVE") (pin "39") (pinfunction "39_39") (pintype "bidirectional"))
    )
    (net (code "202") (name "unconnected-(DRIVE-Pad40)") (class "Default")
      (node (ref "DRIVE") (pin "40") (pinfunction "40_40") (pintype "bidirectional"))
    )
    (net (code "203") (name "unconnected-(DRIVE-Pad41)") (class "Default")
      (node (ref "DRIVE") (pin "41") (pinfunction "41_41") (pintype "bidirectional"))
    )
    (net (code "204") (name "unconnected-(DRIVE-Pad46)") (class "Default")
      (node (ref "DRIVE") (pin "46") (pinfunction "46_46") (pintype "bidirectional"))
    )
    (net (code "205") (name "unconnected-(DRIVE-Pad47)") (class "Default")
      (node (ref "DRIVE") (pin "47") (pinfunction "47_47") (pintype "bidirectional"))
    )
    (net (code "206") (name "unconnected-(DRIVE-Pad48)") (class "Default")
      (node (ref "DRIVE") (pin "48") (pinfunction "48_48") (pintype "bidirectional"))
    )
    (net (code "207") (name "unconnected-(DRIVE-Pad49)") (class "Default")
      (node (ref "DRIVE") (pin "49") (pinfunction "49_49") (pintype "bidirectional"))
    )
    (net (code "208") (name "unconnected-(DRIVE-Pad50)") (class "Default")
      (node (ref "DRIVE") (pin "50") (pinfunction "50_50") (pintype "bidirectional"))
    )
    (net (code "209") (name "unconnected-(DRIVE-Pad51)") (class "Default")
      (node (ref "DRIVE") (pin "51") (pinfunction "51_51") (pintype "bidirectional"))
    )
    (net (code "210") (name "unconnected-(DRIVE-Pad52)") (class "Default")
      (node (ref "DRIVE") (pin "52") (pinfunction "52_52") (pintype "bidirectional"))
    )
    (net (code "211") (name "unconnected-(DRIVE-Pad53)") (class "Default")
      (node (ref "DRIVE") (pin "53") (pinfunction "53_53") (pintype "bidirectional"))
    )
    (net (code "212") (name "unconnected-(DRIVE-PadA0)") (class "Default")
      (node (ref "DRIVE") (pin "A0") (pinfunction "A0_A0") (pintype "bidirectional"))
    )
    (net (code "213") (name "unconnected-(DRIVE-PadA1)") (class "Default")
      (node (ref "DRIVE") (pin "A1") (pinfunction "A1_A1") (pintype "bidirectional"))
    )
    (net (code "214") (name "unconnected-(DRIVE-PadA2)") (class "Default")
      (node (ref "DRIVE") (pin "A2") (pinfunction "A2_A2") (pintype "bidirectional"))
    )
    (net (code "215") (name "unconnected-(DRIVE-PadA3)") (class "Default")
      (node (ref "DRIVE") (pin "A3") (pinfunction "A3_A3") (pintype "bidirectional"))
    )
    (net (code "216") (name "unconnected-(DRIVE-PadA4)") (class "Default")
      (node (ref "DRIVE") (pin "A4") (pinfunction "A4_A4") (pintype "bidirectional"))
    )
    (net (code "217") (name "unconnected-(DRIVE-PadA5)") (class "Default")
      (node (ref "DRIVE") (pin "A5") (pinfunction "A5_A5") (pintype "bidirectional"))
    )
    (net (code "218") (name "unconnected-(DRIVE-PadA6)") (class "Default")
      (node (ref "DRIVE") (pin "A6") (pinfunction "A6_A6") (pintype "bidirectional"))
    )
    (net (code "219") (name "unconnected-(DRIVE-PadA7)") (class "Default")
      (node (ref "DRIVE") (pin "A7") (pinfunction "A7_A7") (pintype "bidirectional"))
    )
    (net (code "220") (name "unconnected-(DRIVE-PadA8)") (class "Default")
      (node (ref "DRIVE") (pin "A8") (pinfunction "A8_A8") (pintype "bidirectional"))
    )
    (net (code "221") (name "unconnected-(DRIVE-PadA9)") (class "Default")
      (node (ref "DRIVE") (pin "A9") (pinfunction "A9_A9") (pintype "bidirectional"))
    )
    (net (code "222") (name "unconnected-(DRIVE-PadA10)") (class "Default")
      (node (ref "DRIVE") (pin "A10") (pinfunction "A10_A10") (pintype "bidirectional"))
    )
    (net (code "223") (name "unconnected-(DRIVE-PadA11)") (class "Default")
      (node (ref "DRIVE") (pin "A11") (pinfunction "A11_A11") (pintype "bidirectional"))
    )
    (net (code "224") (name "unconnected-(DRIVE-PadAREF)") (class "Default")
      (node (ref "DRIVE") (pin "AREF") (pinfunction "AREF_AREF") (pintype "bidirectional"))
    )
    (net (code "225") (name "unconnected-(DRIVE-PadCANRX)") (class "Default")
      (node (ref "DRIVE") (pin "CANRX") (pinfunction "CANRX_CANRX") (pintype "bidirectional"))
    )
    (net (code "226") (name "unconnected-(DRIVE-PadCANTX)") (class "Default")
      (node (ref "DRIVE") (pin "CANTX") (pinfunction "CANTX_CANTX") (pintype "bidirectional"))
    )
    (net (code "227") (name "unconnected-(DRIVE-PadDAC0)") (class "Default")
      (node (ref "DRIVE") (pin "DAC0") (pinfunction "DAC0_DAC0") (pintype "bidirectional"))
    )
    (net (code "228") (name "unconnected-(DRIVE-PadDAC1)") (class "Default")
      (node (ref "DRIVE") (pin "DAC1") (pinfunction "DAC1_DAC1") (pintype "bidirectional"))
    )
    (net (code "229") (name "unconnected-(DRIVE-PadGND_DEBUG)") (class "Default")
      (node (ref "DRIVE") (pin "GND_DEBUG") (pinfunction "GND_DEBUG_GND_DEBUG") (pintype "bidirectional"))
    )
    (net (code "230") (name "unconnected-(DRIVE-PadGND_ICSP)") (class "Default")
      (node (ref "DRIVE") (pin "GND_ICSP") (pinfunction "GND_ICSP_GND_ICSP") (pintype "bidirectional"))
    )
    (net (code "231") (name "unconnected-(DRIVE-PadIOREF)") (class "Default")
      (node (ref "DRIVE") (pin "IOREF") (pinfunction "IOREF_IOREF") (pintype "bidirectional"))
    )
    (net (code "232") (name "unconnected-(DRIVE-PadMISO_ICSP)") (class "Default")
      (node (ref "DRIVE") (pin "MISO_ICSP") (pinfunction "MISO_ICSP_MISO_ICSP") (pintype "bidirectional"))
    )
    (net (code "233") (name "unconnected-(DRIVE-PadMOSI_ICSP)") (class "Default")
      (node (ref "DRIVE") (pin "MOSI_ICSP") (pinfunction "MOSI_ICSP_MOSI_ICSP") (pintype "bidirectional"))
    )
    (net (code "234") (name "unconnected-(DRIVE-PadNC)") (class "Default")
      (node (ref "DRIVE") (pin "NC") (pinfunction "NC_NC") (pintype "bidirectional"))
    )
    (net (code "235") (name "unconnected-(DRIVE-PadRESET_DEBUG)") (class "Default")
      (node (ref "DRIVE") (pin "RESET_DEBUG") (pinfunction "RESET_DEBUG_RESET_DEBUG") (pintype "bidirectional"))
    )
    (net (code "236") (name "unconnected-(DRIVE-PadRESET_ICSP)") (class "Default")
      (node (ref "DRIVE") (pin "RESET_ICSP") (pinfunction "RESET_ICSP_RESET_ICSP") (pintype "bidirectional"))
    )
    (net (code "237") (name "unconnected-(DRIVE-PadRX0)") (class "Default")
      (node (ref "DRIVE") (pin "RX0") (pinfunction "RX0_RX0") (pintype "bidirectional"))
    )
    (net (code "238") (name "unconnected-(DRIVE-PadRX1)") (class "Default")
      (node (ref "DRIVE") (pin "RX1") (pinfunction "RX1_RX1") (pintype "bidirectional"))
    )
    (net (code "239") (name "unconnected-(DRIVE-PadRX2)") (class "Default")
      (node (ref "DRIVE") (pin "RX2") (pinfunction "RX2_RX2") (pintype "bidirectional"))
    )
    (net (code "240") (name "unconnected-(DRIVE-PadRX3)") (class "Default")
      (node (ref "DRIVE") (pin "RX3") (pinfunction "RX3_RX3") (pintype "bidirectional"))
    )
    (net (code "241") (name "unconnected-(DRIVE-PadSCK_ICSP)") (class "Default")
      (node (ref "DRIVE") (pin "SCK_ICSP") (pinfunction "SCK_ICSP_SCK_ICSP") (pintype "bidirectional"))
    )
    (net (code "242") (name "unconnected-(DRIVE-PadSCL1)") (class "Default")
      (node (ref "DRIVE") (pin "SCL1") (pinfunction "SCL1_SCL1") (pintype "bidirectional"))
    )
    (net (code "243") (name "unconnected-(DRIVE-PadSDA1)") (class "Default")
      (node (ref "DRIVE") (pin "SDA1") (pinfunction "SDA1_SDA1") (pintype "bidirectional"))
    )
    (net (code "244") (name "unconnected-(DRIVE-PadSWCLK_DEBUG)") (class "Default")
      (node (ref "DRIVE") (pin "SWCLK_DEBUG") (pinfunction "SWCLK_DEBUG_SWCLK_DEBUG") (pintype "bidirectional"))
    )
    (net (code "245") (name "unconnected-(DRIVE-PadSWDIO_DEBUG)") (class "Default")
      (node (ref "DRIVE") (pin "SWDIO_DEBUG") (pinfunction "SWDIO_DEBUG_SWDIO_DEBUG") (pintype "bidirectional"))
    )
    (net (code "246") (name "unconnected-(DRIVE-PadTX0)") (class "Default")
      (node (ref "DRIVE") (pin "TX0") (pinfunction "TX0_TX0") (pintype "bidirectional"))
    )
    (net (code "247") (name "unconnected-(DRIVE-PadTX1)") (class "Default")
      (node (ref "DRIVE") (pin "TX1") (pinfunction "TX1_TX1") (pintype "bidirectional"))
    )
    (net (code "248") (name "unconnected-(DRIVE-PadTX2)") (class "Default")
      (node (ref "DRIVE") (pin "TX2") (pinfunction "TX2_TX2") (pintype "bidirectional"))
    )
    (net (code "249") (name "unconnected-(DRIVE-PadTX3)") (class "Default")
      (node (ref "DRIVE") (pin "TX3") (pinfunction "TX3_TX3") (pintype "bidirectional"))
    )
    (net (code "250") (name "unconnected-(S4-P1-Pad4)") (class "Default")
      (node (ref "S4") (pin "4") (pinfunction "P1_4") (pintype "passive"))
    )
    (net (code "251") (name "unconnected-(S4-S1-Pad2)") (class "Default")
      (node (ref "S4") (pin "2") (pinfunction "S1_2") (pintype "passive"))
    )
    (net (code "252") (name "unconnected-(SCIENCE-Pad2)") (class "Default")
      (node (ref "SCIENCE") (pin "2") (pinfunction "2_2") (pintype "bidirectional"))
    )
    (net (code "253") (name "unconnected-(SCIENCE-Pad3)") (class "Default")
      (node (ref "SCIENCE") (pin "3") (pinfunction "3_3") (pintype "bidirectional"))
    )
    (net (code "254") (name "unconnected-(SCIENCE-Pad3V3)") (class "Default")
      (node (ref "SCIENCE") (pin "3V3") (pinfunction "3V3_3V3") (pintype "bidirectional"))
    )
    (net (code "255") (name "unconnected-(SCIENCE-Pad4)") (class "Default")
      (node (ref "SCIENCE") (pin "4") (pinfunction "4_4") (pintype "bidirectional"))
    )
    (net (code "256") (name "unconnected-(SCIENCE-Pad5)") (class "Default")
      (node (ref "SCIENCE") (pin "5") (pinfunction "5_5") (pintype "bidirectional"))
    )
    (net (code "257") (name "unconnected-(SCIENCE-Pad5V)") (class "Default")
      (node (ref "SCIENCE") (pin "5V") (pinfunction "5V_5V") (pintype "bidirectional"))
    )
    (net (code "258") (name "unconnected-(SCIENCE-Pad5V_A)") (class "Default")
      (node (ref "SCIENCE") (pin "5V_A") (pinfunction "5V_A_5V_A") (pintype "bidirectional"))
    )
    (net (code "259") (name "unconnected-(SCIENCE-Pad5V_B)") (class "Default")
      (node (ref "SCIENCE") (pin "5V_B") (pinfunction "5V_B_5V_B") (pintype "bidirectional"))
    )
    (net (code "260") (name "unconnected-(SCIENCE-Pad6)") (class "Default")
      (node (ref "SCIENCE") (pin "6") (pinfunction "6_6") (pintype "bidirectional"))
    )
    (net (code "261") (name "unconnected-(SCIENCE-Pad7)") (class "Default")
      (node (ref "SCIENCE") (pin "7") (pinfunction "7_7") (pintype "bidirectional"))
    )
    (net (code "262") (name "unconnected-(SCIENCE-Pad8)") (class "Default")
      (node (ref "SCIENCE") (pin "8") (pinfunction "8_8") (pintype "bidirectional"))
    )
    (net (code "263") (name "unconnected-(SCIENCE-Pad9)") (class "Default")
      (node (ref "SCIENCE") (pin "9") (pinfunction "9_9") (pintype "bidirectional"))
    )
    (net (code "264") (name "unconnected-(SCIENCE-Pad10)") (class "Default")
      (node (ref "SCIENCE") (pin "10") (pinfunction "10_10") (pintype "bidirectional"))
    )
    (net (code "265") (name "unconnected-(SCIENCE-Pad11)") (class "Default")
      (node (ref "SCIENCE") (pin "11") (pinfunction "11_11") (pintype "bidirectional"))
    )
    (net (code "266") (name "unconnected-(SCIENCE-Pad12)") (class "Default")
      (node (ref "SCIENCE") (pin "12") (pinfunction "12_12") (pintype "bidirectional"))
    )
    (net (code "267") (name "unconnected-(SCIENCE-Pad13)") (class "Default")
      (node (ref "SCIENCE") (pin "13") (pinfunction "13_13") (pintype "bidirectional"))
    )
    (net (code "268") (name "unconnected-(SCIENCE-Pad22)") (class "Default")
      (node (ref "SCIENCE") (pin "22") (pinfunction "22_22") (pintype "bidirectional"))
    )
    (net (code "269") (name "unconnected-(SCIENCE-Pad23)") (class "Default")
      (node (ref "SCIENCE") (pin "23") (pinfunction "23_23") (pintype "bidirectional"))
    )
    (net (code "270") (name "unconnected-(SCIENCE-Pad24)") (class "Default")
      (node (ref "SCIENCE") (pin "24") (pinfunction "24_24") (pintype "bidirectional"))
    )
    (net (code "271") (name "unconnected-(SCIENCE-Pad25)") (class "Default")
      (node (ref "SCIENCE") (pin "25") (pinfunction "25_25") (pintype "bidirectional"))
    )
    (net (code "272") (name "unconnected-(SCIENCE-Pad26)") (class "Default")
      (node (ref "SCIENCE") (pin "26") (pinfunction "26_26") (pintype "bidirectional"))
    )
    (net (code "273") (name "unconnected-(SCIENCE-Pad27)") (class "Default")
      (node (ref "SCIENCE") (pin "27") (pinfunction "27_27") (pintype "bidirectional"))
    )
    (net (code "274") (name "unconnected-(SCIENCE-Pad28)") (class "Default")
      (node (ref "SCIENCE") (pin "28") (pinfunction "28_28") (pintype "bidirectional"))
    )
    (net (code "275") (name "unconnected-(SCIENCE-Pad29)") (class "Default")
      (node (ref "SCIENCE") (pin "29") (pinfunction "29_29") (pintype "bidirectional"))
    )
    (net (code "276") (name "unconnected-(SCIENCE-Pad30)") (class "Default")
      (node (ref "SCIENCE") (pin "30") (pinfunction "30_30") (pintype "bidirectional"))
    )
    (net (code "277") (name "unconnected-(SCIENCE-Pad31)") (class "Default")
      (node (ref "SCIENCE") (pin "31") (pinfunction "31_31") (pintype "bidirectional"))
    )
    (net (code "278") (name "unconnected-(SCIENCE-Pad32)") (class "Default")
      (node (ref "SCIENCE") (pin "32") (pinfunction "32_32") (pintype "bidirectional"))
    )
    (net (code "279") (name "unconnected-(SCIENCE-Pad33)") (class "Default")
      (node (ref "SCIENCE") (pin "33") (pinfunction "33_33") (pintype "bidirectional"))
    )
    (net (code "280") (name "unconnected-(SCIENCE-Pad34)") (class "Default")
      (node (ref "SCIENCE") (pin "34") (pinfunction "34_34") (pintype "bidirectional"))
    )
    (net (code "281") (name "unconnected-(SCIENCE-Pad35)") (class "Default")
      (node (ref "SCIENCE") (pin "35") (pinfunction "35_35") (pintype "bidirectional"))
    )
    (net (code "282") (name "unconnected-(SCIENCE-Pad36)") (class "Default")
      (node (ref "SCIENCE") (pin "36") (pinfunction "36_36") (pintype "bidirectional"))
    )
    (net (code "283") (name "unconnected-(SCIENCE-Pad37)") (class "Default")
      (node (ref "SCIENCE") (pin "37") (pinfunction "37_37") (pintype "bidirectional"))
    )
    (net (code "284") (name "unconnected-(SCIENCE-Pad38)") (class "Default")
      (node (ref "SCIENCE") (pin "38") (pinfunction "38_38") (pintype "bidirectional"))
    )
    (net (code "285") (name "unconnected-(SCIENCE-Pad39)") (class "Default")
      (node (ref "SCIENCE") (pin "39") (pinfunction "39_39") (pintype "bidirectional"))
    )
    (net (code "286") (name "unconnected-(SCIENCE-Pad40)") (class "Default")
      (node (ref "SCIENCE") (pin "40") (pinfunction "40_40") (pintype "bidirectional"))
    )
    (net (code "287") (name "unconnected-(SCIENCE-Pad41)") (class "Default")
      (node (ref "SCIENCE") (pin "41") (pinfunction "41_41") (pintype "bidirectional"))
    )
    (net (code "288") (name "unconnected-(SCIENCE-Pad46)") (class "Default")
      (node (ref "SCIENCE") (pin "46") (pinfunction "46_46") (pintype "bidirectional"))
    )
    (net (code "289") (name "unconnected-(SCIENCE-Pad47)") (class "Default")
      (node (ref "SCIENCE") (pin "47") (pinfunction "47_47") (pintype "bidirectional"))
    )
    (net (code "290") (name "unconnected-(SCIENCE-Pad48)") (class "Default")
      (node (ref "SCIENCE") (pin "48") (pinfunction "48_48") (pintype "bidirectional"))
    )
    (net (code "291") (name "unconnected-(SCIENCE-Pad49)") (class "Default")
      (node (ref "SCIENCE") (pin "49") (pinfunction "49_49") (pintype "bidirectional"))
    )
    (net (code "292") (name "unconnected-(SCIENCE-Pad50)") (class "Default")
      (node (ref "SCIENCE") (pin "50") (pinfunction "50_50") (pintype "bidirectional"))
    )
    (net (code "293") (name "unconnected-(SCIENCE-Pad51)") (class "Default")
      (node (ref "SCIENCE") (pin "51") (pinfunction "51_51") (pintype "bidirectional"))
    )
    (net (code "294") (name "unconnected-(SCIENCE-Pad52)") (class "Default")
      (node (ref "SCIENCE") (pin "52") (pinfunction "52_52") (pintype "bidirectional"))
    )
    (net (code "295") (name "unconnected-(SCIENCE-Pad53)") (class "Default")
      (node (ref "SCIENCE") (pin "53") (pinfunction "53_53") (pintype "bidirectional"))
    )
    (net (code "296") (name "unconnected-(SCIENCE-PadA0)") (class "Default")
      (node (ref "SCIENCE") (pin "A0") (pinfunction "A0_A0") (pintype "bidirectional"))
    )
    (net (code "297") (name "unconnected-(SCIENCE-PadA1)") (class "Default")
      (node (ref "SCIENCE") (pin "A1") (pinfunction "A1_A1") (pintype "bidirectional"))
    )
    (net (code "298") (name "unconnected-(SCIENCE-PadA2)") (class "Default")
      (node (ref "SCIENCE") (pin "A2") (pinfunction "A2_A2") (pintype "bidirectional"))
    )
    (net (code "299") (name "unconnected-(SCIENCE-PadA3)") (class "Default")
      (node (ref "SCIENCE") (pin "A3") (pinfunction "A3_A3") (pintype "bidirectional"))
    )
    (net (code "300") (name "unconnected-(SCIENCE-PadA4)") (class "Default")
      (node (ref "SCIENCE") (pin "A4") (pinfunction "A4_A4") (pintype "bidirectional"))
    )
    (net (code "301") (name "unconnected-(SCIENCE-PadA5)") (class "Default")
      (node (ref "SCIENCE") (pin "A5") (pinfunction "A5_A5") (pintype "bidirectional"))
    )
    (net (code "302") (name "unconnected-(SCIENCE-PadA6)") (class "Default")
      (node (ref "SCIENCE") (pin "A6") (pinfunction "A6_A6") (pintype "bidirectional"))
    )
    (net (code "303") (name "unconnected-(SCIENCE-PadA7)") (class "Default")
      (node (ref "SCIENCE") (pin "A7") (pinfunction "A7_A7") (pintype "bidirectional"))
    )
    (net (code "304") (name "unconnected-(SCIENCE-PadA8)") (class "Default")
      (node (ref "SCIENCE") (pin "A8") (pinfunction "A8_A8") (pintype "bidirectional"))
    )
    (net (code "305") (name "unconnected-(SCIENCE-PadA9)") (class "Default")
      (node (ref "SCIENCE") (pin "A9") (pinfunction "A9_A9") (pintype "bidirectional"))
    )
    (net (code "306") (name "unconnected-(SCIENCE-PadA10)") (class "Default")
      (node (ref "SCIENCE") (pin "A10") (pinfunction "A10_A10") (pintype "bidirectional"))
    )
    (net (code "307") (name "unconnected-(SCIENCE-PadA11)") (class "Default")
      (node (ref "SCIENCE") (pin "A11") (pinfunction "A11_A11") (pintype "bidirectional"))
    )
    (net (code "308") (name "unconnected-(SCIENCE-PadAREF)") (class "Default")
      (node (ref "SCIENCE") (pin "AREF") (pinfunction "AREF_AREF") (pintype "bidirectional"))
    )
    (net (code "309") (name "unconnected-(SCIENCE-PadCANRX)") (class "Default")
      (node (ref "SCIENCE") (pin "CANRX") (pinfunction "CANRX_CANRX") (pintype "bidirectional"))
    )
    (net (code "310") (name "unconnected-(SCIENCE-PadCANTX)") (class "Default")
      (node (ref "SCIENCE") (pin "CANTX") (pinfunction "CANTX_CANTX") (pintype "bidirectional"))
    )
    (net (code "311") (name "unconnected-(SCIENCE-PadDAC0)") (class "Default")
      (node (ref "SCIENCE") (pin "DAC0") (pinfunction "DAC0_DAC0") (pintype "bidirectional"))
    )
    (net (code "312") (name "unconnected-(SCIENCE-PadDAC1)") (class "Default")
      (node (ref "SCIENCE") (pin "DAC1") (pinfunction "DAC1_DAC1") (pintype "bidirectional"))
    )
    (net (code "313") (name "unconnected-(SCIENCE-PadGND_DEBUG)") (class "Default")
      (node (ref "SCIENCE") (pin "GND_DEBUG") (pinfunction "GND_DEBUG_GND_DEBUG") (pintype "bidirectional"))
    )
    (net (code "314") (name "unconnected-(SCIENCE-PadGND_ICSP)") (class "Default")
      (node (ref "SCIENCE") (pin "GND_ICSP") (pinfunction "GND_ICSP_GND_ICSP") (pintype "bidirectional"))
    )
    (net (code "315") (name "unconnected-(SCIENCE-PadIOREF)") (class "Default")
      (node (ref "SCIENCE") (pin "IOREF") (pinfunction "IOREF_IOREF") (pintype "bidirectional"))
    )
    (net (code "316") (name "unconnected-(SCIENCE-PadMISO_ICSP)") (class "Default")
      (node (ref "SCIENCE") (pin "MISO_ICSP") (pinfunction "MISO_ICSP_MISO_ICSP") (pintype "bidirectional"))
    )
    (net (code "317") (name "unconnected-(SCIENCE-PadMOSI_ICSP)") (class "Default")
      (node (ref "SCIENCE") (pin "MOSI_ICSP") (pinfunction "MOSI_ICSP_MOSI_ICSP") (pintype "bidirectional"))
    )
    (net (code "318") (name "unconnected-(SCIENCE-PadNC)") (class "Default")
      (node (ref "SCIENCE") (pin "NC") (pinfunction "NC_NC") (pintype "bidirectional"))
    )
    (net (code "319") (name "unconnected-(SCIENCE-PadRESET_DEBUG)") (class "Default")
      (node (ref "SCIENCE") (pin "RESET_DEBUG") (pinfunction "RESET_DEBUG_RESET_DEBUG") (pintype "bidirectional"))
    )
    (net (code "320") (name "unconnected-(SCIENCE-PadRESET_ICSP)") (class "Default")
      (node (ref "SCIENCE") (pin "RESET_ICSP") (pinfunction "RESET_ICSP_RESET_ICSP") (pintype "bidirectional"))
    )
    (net (code "321") (name "unconnected-(SCIENCE-PadRX0)") (class "Default")
      (node (ref "SCIENCE") (pin "RX0") (pinfunction "RX0_RX0") (pintype "bidirectional"))
    )
    (net (code "322") (name "unconnected-(SCIENCE-PadRX1)") (class "Default")
      (node (ref "SCIENCE") (pin "RX1") (pinfunction "RX1_RX1") (pintype "bidirectional"))
    )
    (net (code "323") (name "unconnected-(SCIENCE-PadRX2)") (class "Default")
      (node (ref "SCIENCE") (pin "RX2") (pinfunction "RX2_RX2") (pintype "bidirectional"))
    )
    (net (code "324") (name "unconnected-(SCIENCE-PadRX3)") (class "Default")
      (node (ref "SCIENCE") (pin "RX3") (pinfunction "RX3_RX3") (pintype "bidirectional"))
    )
    (net (code "325") (name "unconnected-(SCIENCE-PadSCK_ICSP)") (class "Default")
      (node (ref "SCIENCE") (pin "SCK_ICSP") (pinfunction "SCK_ICSP_SCK_ICSP") (pintype "bidirectional"))
    )
    (net (code "326") (name "unconnected-(SCIENCE-PadSWCLK_DEBUG)") (class "Default")
      (node (ref "SCIENCE") (pin "SWCLK_DEBUG") (pinfunction "SWCLK_DEBUG_SWCLK_DEBUG") (pintype "bidirectional"))
    )
    (net (code "327") (name "unconnected-(SCIENCE-PadSWDIO_DEBUG)") (class "Default")
      (node (ref "SCIENCE") (pin "SWDIO_DEBUG") (pinfunction "SWDIO_DEBUG_SWDIO_DEBUG") (pintype "bidirectional"))
    )
    (net (code "328") (name "unconnected-(SCIENCE-PadTX0)") (class "Default")
      (node (ref "SCIENCE") (pin "TX0") (pinfunction "TX0_TX0") (pintype "bidirectional"))
    )
    (net (code "329") (name "unconnected-(SCIENCE-PadTX1)") (class "Default")
      (node (ref "SCIENCE") (pin "TX1") (pinfunction "TX1_TX1") (pintype "bidirectional"))
    )
    (net (code "330") (name "unconnected-(SCIENCE-PadTX2)") (class "Default")
      (node (ref "SCIENCE") (pin "TX2") (pinfunction "TX2_TX2") (pintype "bidirectional"))
    )
    (net (code "331") (name "unconnected-(SCIENCE-PadTX3)") (class "Default")
      (node (ref "SCIENCE") (pin "TX3") (pinfunction "TX3_TX3") (pintype "bidirectional"))
    )
    (net (code "332") (name "unconnected-(TX2HEADER-Pad2)") (class "Default")
      (node (ref "TX2HEADER") (pin "2") (pinfunction "2_2") (pintype "passive"))
    )
    (net (code "333") (name "unconnected-(TX2HEADER-Pad7)") (class "Default")
      (node (ref "TX2HEADER") (pin "7") (pinfunction "7_7") (pintype "passive"))
    )
    (net (code "334") (name "unconnected-(TX2HEADER-Pad8)") (class "Default")
      (node (ref "TX2HEADER") (pin "8") (pinfunction "8_8") (pintype "passive"))
    )
    (net (code "335") (name "unconnected-(TX2HEADER-Pad9)") (class "Default")
      (node (ref "TX2HEADER") (pin "9") (pinfunction "9_9") (pintype "passive"))
    )
    (net (code "336") (name "unconnected-(TX2HEADER-Pad10)") (class "Default")
      (node (ref "TX2HEADER") (pin "10") (pinfunction "10_10") (pintype "passive"))
    )
    (net (code "337") (name "unconnected-(TX2HEADER-Pad13)") (class "Default")
      (node (ref "TX2HEADER") (pin "13") (pinfunction "13_13") (pintype "passive"))
    )
    (net (code "338") (name "unconnected-(TX2HEADER-Pad14)") (class "Default")
      (node (ref "TX2HEADER") (pin "14") (pinfunction "14_14") (pintype "passive"))
    )
    (net (code "339") (name "unconnected-(TX2HEADER-Pad17)") (class "Default")
      (node (ref "TX2HEADER") (pin "17") (pinfunction "17_17") (pintype "passive"))
    )
  )
)
